# LPC4357_SDRAM.net
KiCad netlist of a schematic drawn in Altium Designer
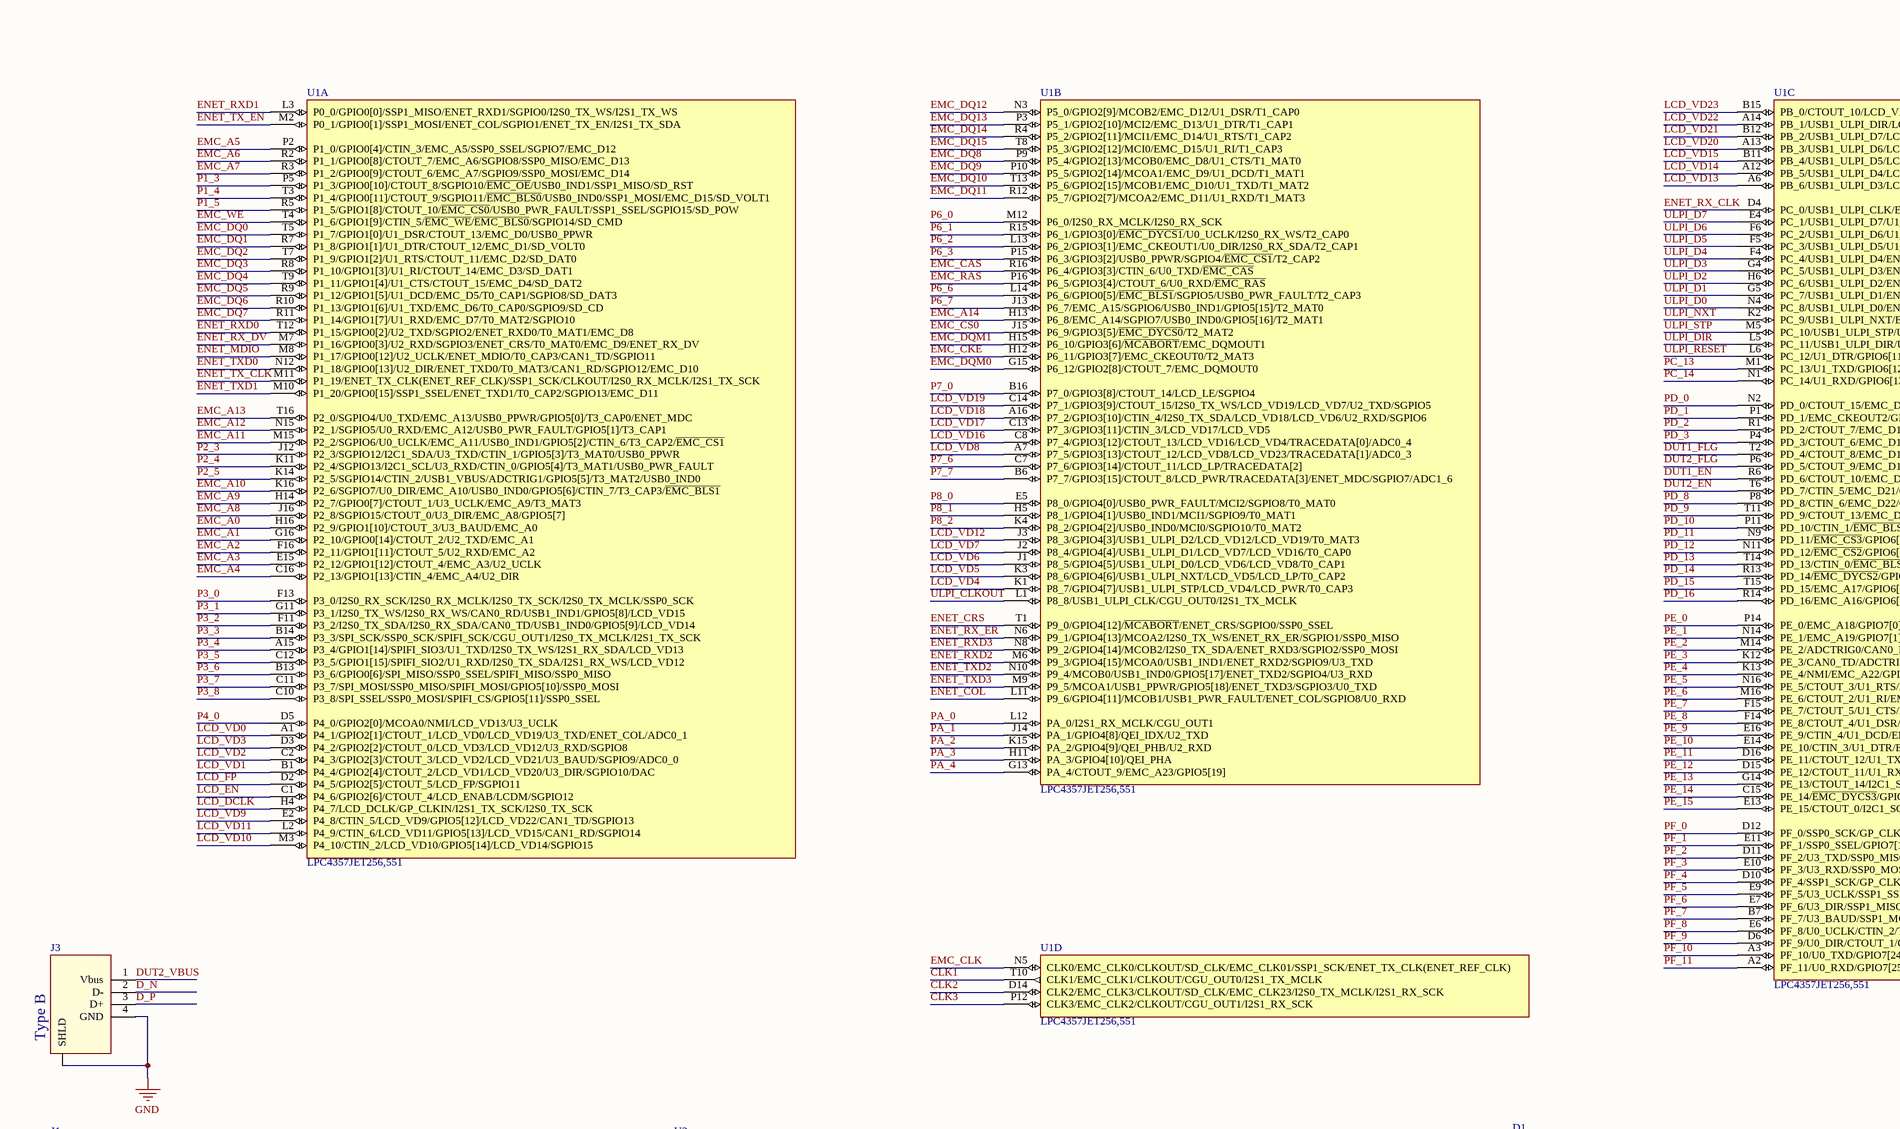
[diagram p0: LPC4357_SDRAM.SchDoc, top left]
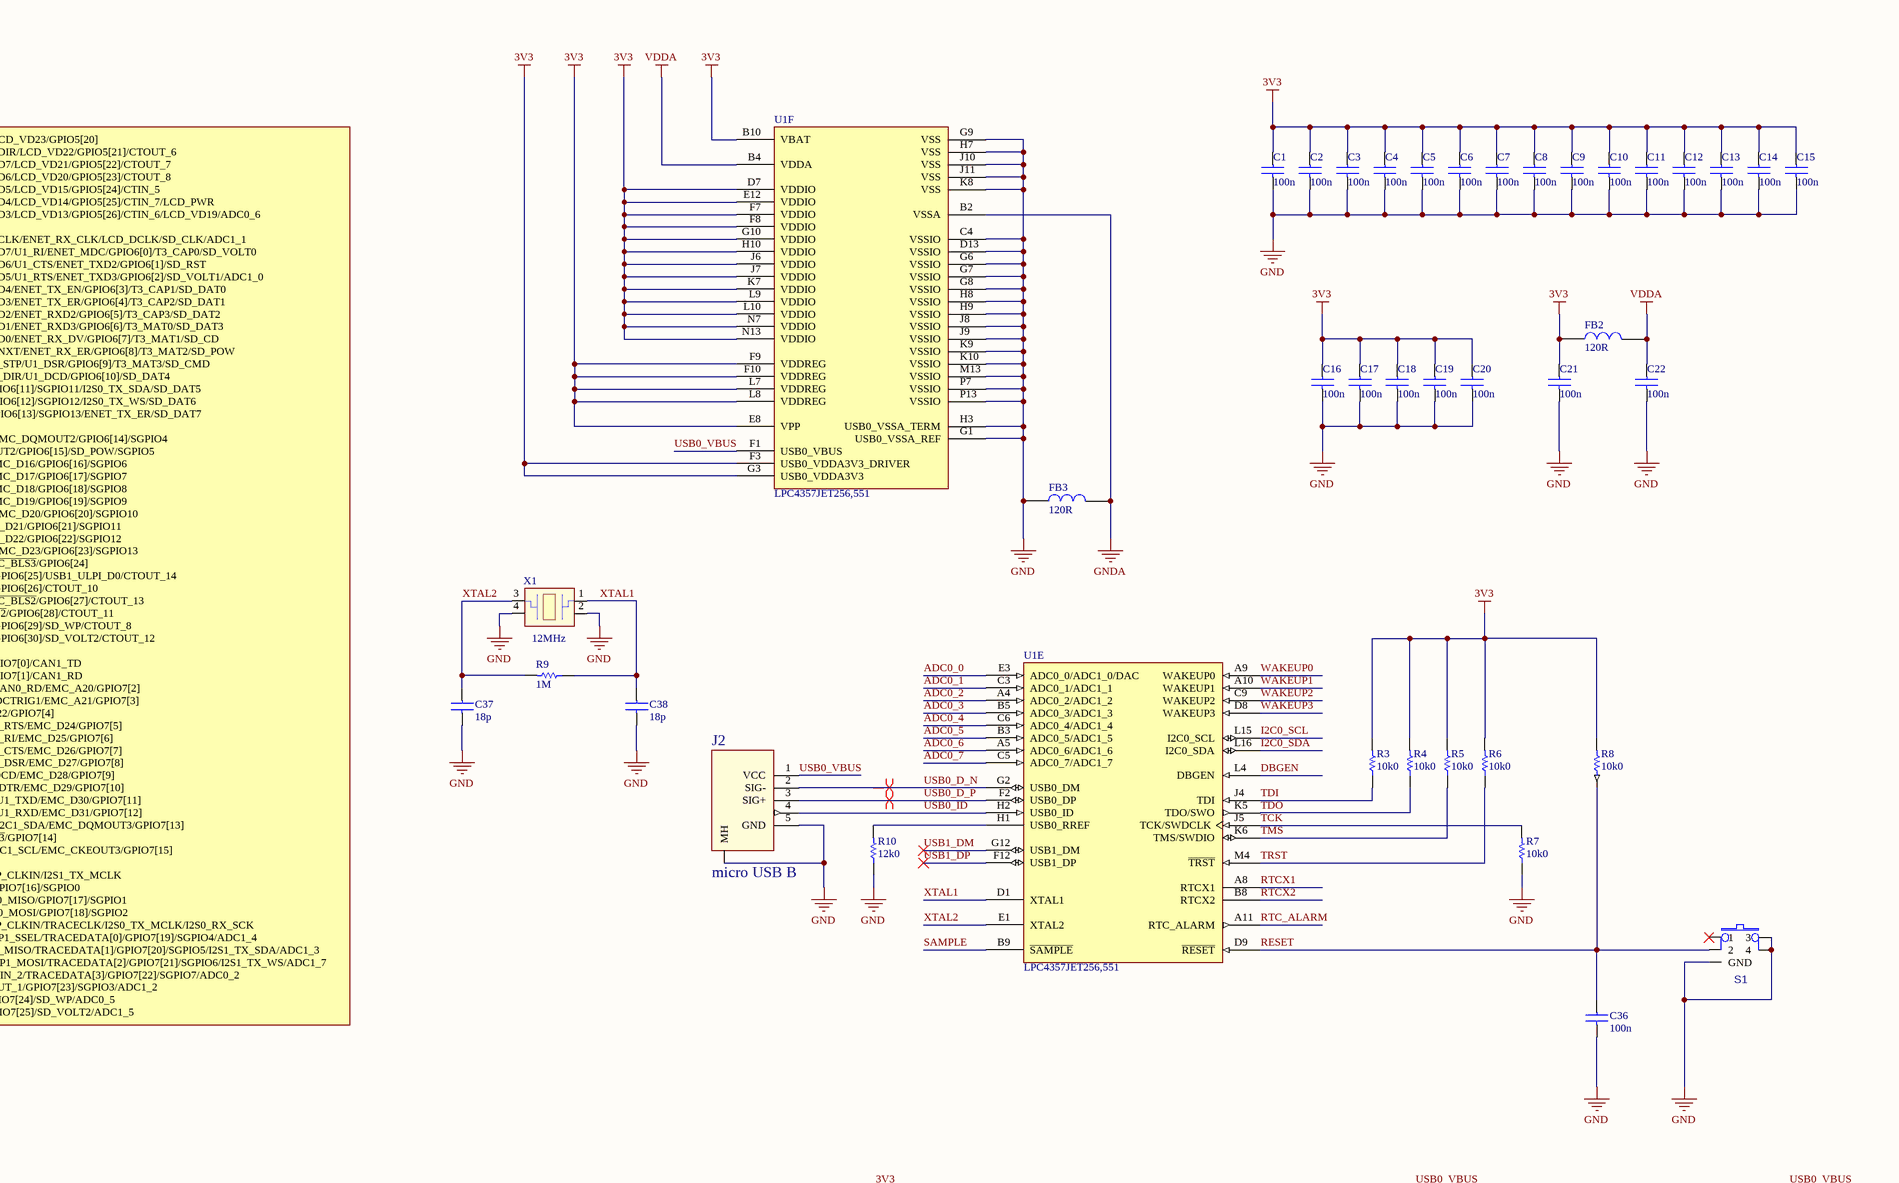
[diagram p1: LPC4357_SDRAM.SchDoc, top right]
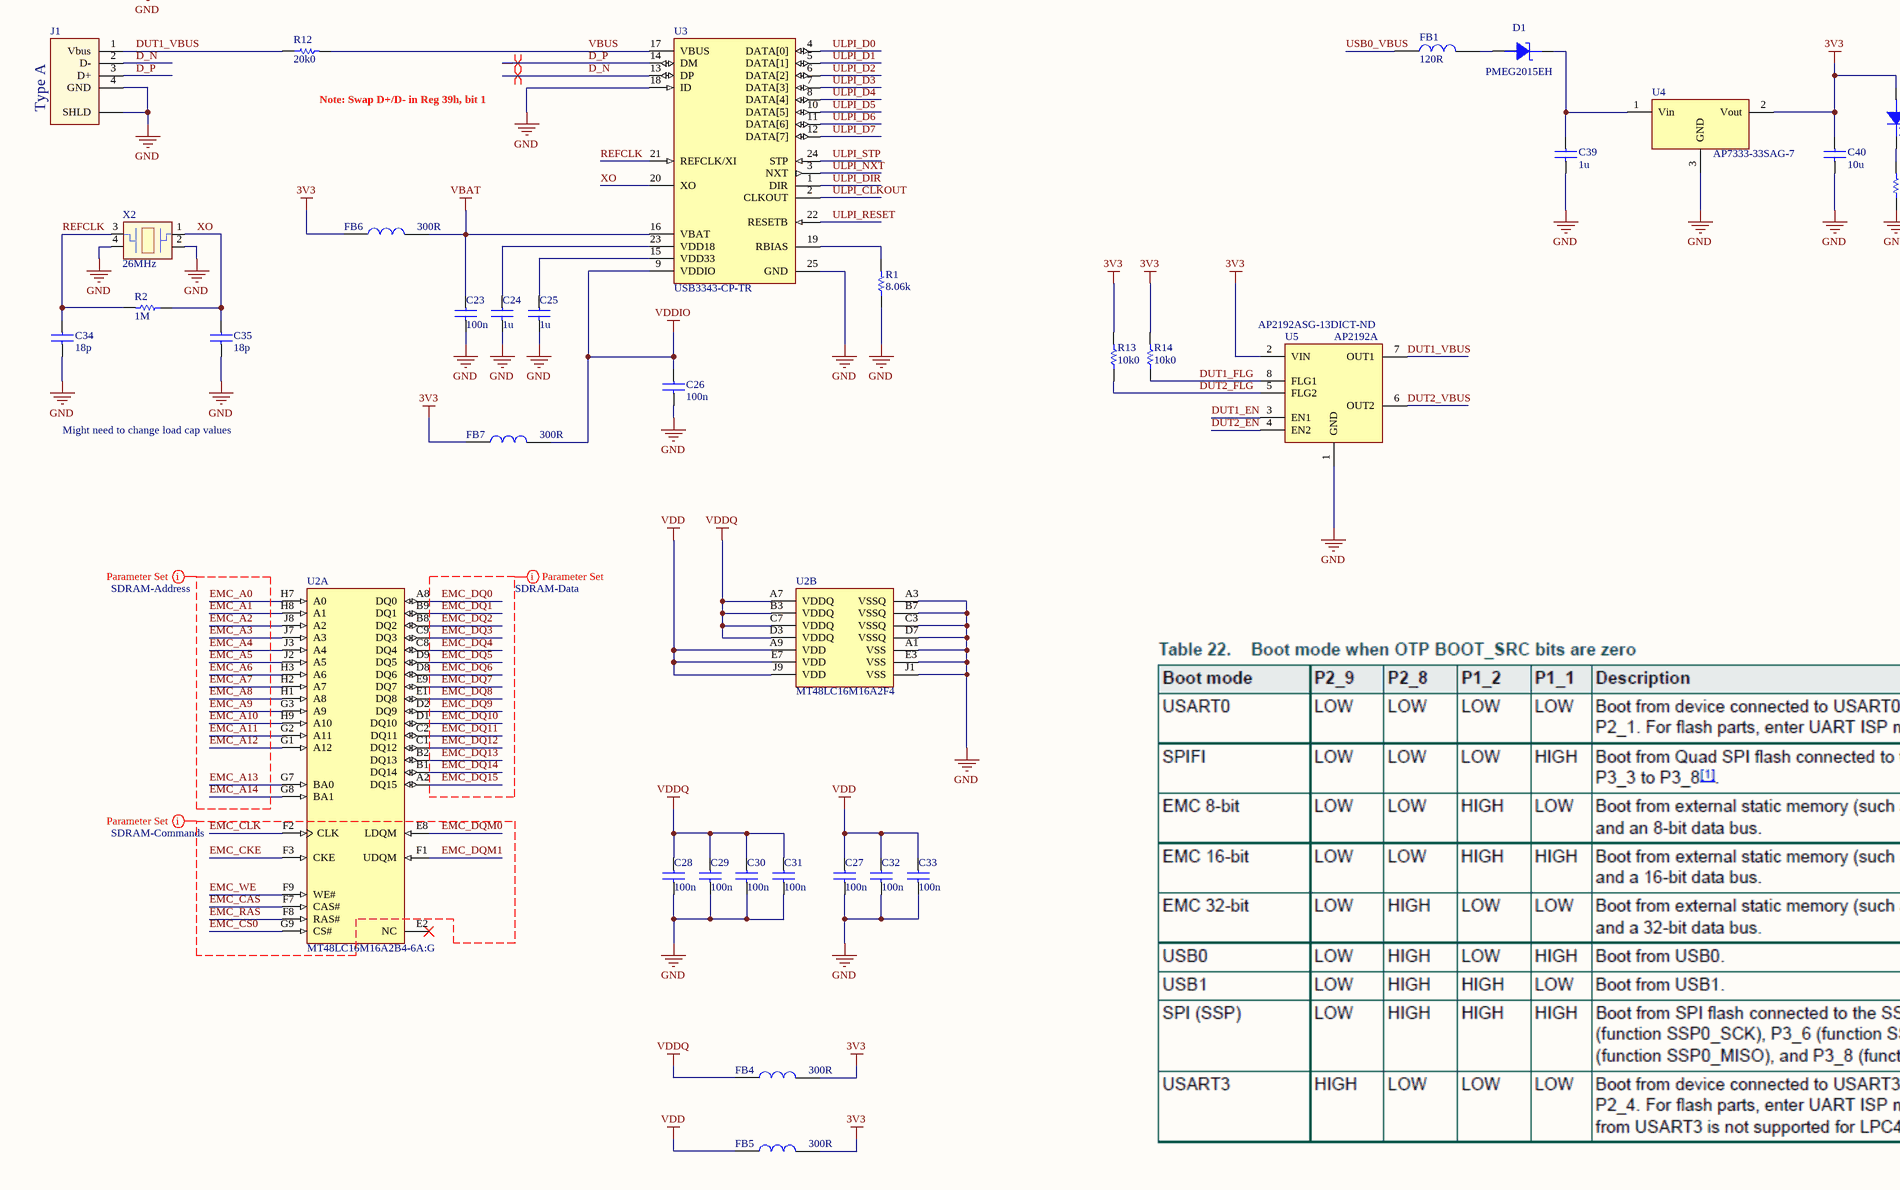
[diagram p2: LPC4357_SDRAM.SchDoc, bottom left]
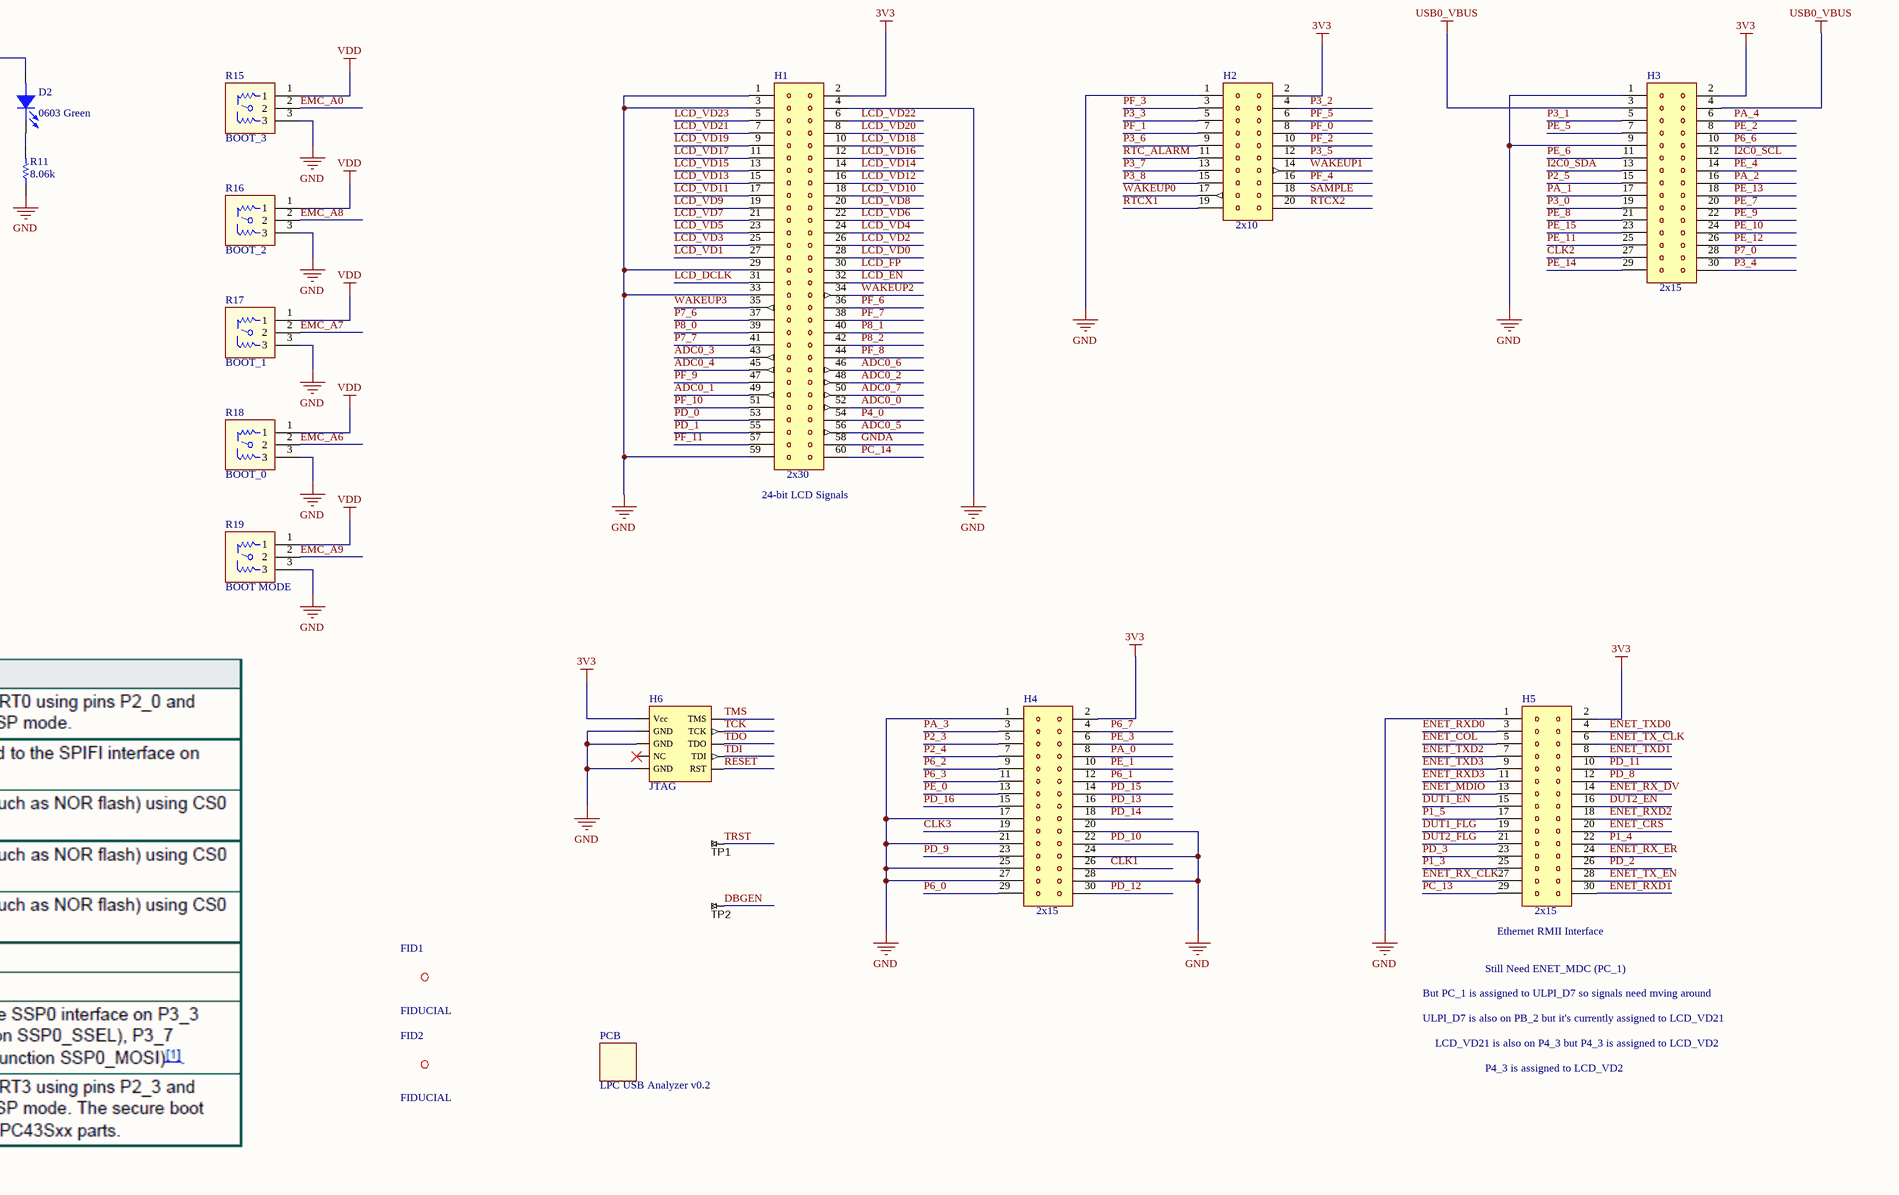
[diagram p3: LPC4357_SDRAM.SchDoc, bottom right]

(export (version "E")
  (design (tool "Eeschema 10.0.6"))
  (components
    (comp (ref "C1")
      (value "100n")
      (footprint "C_0402_N")
      (description "Cap, Chip, 100nF, 16V, ±10%, X7R, 0402")
      (fields (field (name "MANUFACTURER") "NIC"))
      (libsource (lib "GLIB") (part "C_100n_16V_10_0402_NIC"))
    )
    (comp (ref "C2")
      (value "100n")
      (footprint "C_0402_N")
      (description "Cap, Chip, 100nF, 16V, ±10%, X7R, 0402")
      (fields (field (name "MANUFACTURER") "NIC"))
      (libsource (lib "GLIB") (part "C_100n_16V_10_0402_NIC"))
    )
    (comp (ref "C3")
      (value "100n")
      (footprint "C_0402_N")
      (description "Cap, Chip, 100nF, 16V, ±10%, X7R, 0402")
      (fields (field (name "MANUFACTURER") "NIC"))
      (libsource (lib "GLIB") (part "C_100n_16V_10_0402_NIC"))
    )
    (comp (ref "C4")
      (value "100n")
      (footprint "C_0402_N")
      (description "Cap, Chip, 100nF, 16V, ±10%, X7R, 0402")
      (fields (field (name "MANUFACTURER") "NIC"))
      (libsource (lib "GLIB") (part "C_100n_16V_10_0402_NIC"))
    )
    (comp (ref "C5")
      (value "100n")
      (footprint "C_0402_N")
      (description "Cap, Chip, 100nF, 16V, ±10%, X7R, 0402")
      (fields (field (name "MANUFACTURER") "NIC"))
      (libsource (lib "GLIB") (part "C_100n_16V_10_0402_NIC"))
    )
    (comp (ref "C6")
      (value "100n")
      (footprint "C_0402_N")
      (description "Cap, Chip, 100nF, 16V, ±10%, X7R, 0402")
      (fields (field (name "MANUFACTURER") "NIC"))
      (libsource (lib "GLIB") (part "C_100n_16V_10_0402_NIC"))
    )
    (comp (ref "C7")
      (value "100n")
      (footprint "C_0402_N")
      (description "Cap, Chip, 100nF, 16V, ±10%, X7R, 0402")
      (fields (field (name "MANUFACTURER") "NIC"))
      (libsource (lib "GLIB") (part "C_100n_16V_10_0402_NIC"))
    )
    (comp (ref "C8")
      (value "100n")
      (footprint "C_0402_N")
      (description "Cap, Chip, 100nF, 16V, ±10%, X7R, 0402")
      (fields (field (name "MANUFACTURER") "NIC"))
      (libsource (lib "GLIB") (part "C_100n_16V_10_0402_NIC"))
    )
    (comp (ref "C9")
      (value "100n")
      (footprint "C_0402_N")
      (description "Cap, Chip, 100nF, 16V, ±10%, X7R, 0402")
      (fields (field (name "MANUFACTURER") "NIC"))
      (libsource (lib "GLIB") (part "C_100n_16V_10_0402_NIC"))
    )
    (comp (ref "C10")
      (value "100n")
      (footprint "C_0402_N")
      (description "Cap, Chip, 100nF, 16V, ±10%, X7R, 0402")
      (fields (field (name "MANUFACTURER") "NIC"))
      (libsource (lib "GLIB") (part "C_100n_16V_10_0402_NIC"))
    )
    (comp (ref "C11")
      (value "100n")
      (footprint "C_0402_N")
      (description "Cap, Chip, 100nF, 16V, ±10%, X7R, 0402")
      (fields (field (name "MANUFACTURER") "NIC"))
      (libsource (lib "GLIB") (part "C_100n_16V_10_0402_NIC"))
    )
    (comp (ref "C12")
      (value "100n")
      (footprint "C_0402_N")
      (description "Cap, Chip, 100nF, 16V, ±10%, X7R, 0402")
      (fields (field (name "MANUFACTURER") "NIC"))
      (libsource (lib "GLIB") (part "C_100n_16V_10_0402_NIC"))
    )
    (comp (ref "C13")
      (value "100n")
      (footprint "C_0402_N")
      (description "Cap, Chip, 100nF, 16V, ±10%, X7R, 0402")
      (fields (field (name "MANUFACTURER") "NIC"))
      (libsource (lib "GLIB") (part "C_100n_16V_10_0402_NIC"))
    )
    (comp (ref "C14")
      (value "100n")
      (footprint "C_0402_N")
      (description "Cap, Chip, 100nF, 16V, ±10%, X7R, 0402")
      (fields (field (name "MANUFACTURER") "NIC"))
      (libsource (lib "GLIB") (part "C_100n_16V_10_0402_NIC"))
    )
    (comp (ref "C15")
      (value "100n")
      (footprint "C_0402_N")
      (description "Cap, Chip, 100nF, 16V, ±10%, X7R, 0402")
      (fields (field (name "MANUFACTURER") "NIC"))
      (libsource (lib "GLIB") (part "C_100n_16V_10_0402_NIC"))
    )
    (comp (ref "C16")
      (value "100n")
      (footprint "C_0402_N")
      (description "Cap, Chip, 100nF, 16V, ±10%, X7R, 0402")
      (fields (field (name "MANUFACTURER") "NIC"))
      (libsource (lib "GLIB") (part "C_100n_16V_10_0402_NIC"))
    )
    (comp (ref "C17")
      (value "100n")
      (footprint "C_0402_N")
      (description "Cap, Chip, 100nF, 16V, ±10%, X7R, 0402")
      (fields (field (name "MANUFACTURER") "NIC"))
      (libsource (lib "GLIB") (part "C_100n_16V_10_0402_NIC"))
    )
    (comp (ref "C18")
      (value "100n")
      (footprint "C_0402_N")
      (description "Cap, Chip, 100nF, 16V, ±10%, X7R, 0402")
      (fields (field (name "MANUFACTURER") "NIC"))
      (libsource (lib "GLIB") (part "C_100n_16V_10_0402_NIC"))
    )
    (comp (ref "C19")
      (value "100n")
      (footprint "C_0402_N")
      (description "Cap, Chip, 100nF, 16V, ±10%, X7R, 0402")
      (fields (field (name "MANUFACTURER") "NIC"))
      (libsource (lib "GLIB") (part "C_100n_16V_10_0402_NIC"))
    )
    (comp (ref "C20")
      (value "100n")
      (footprint "C_0402_N")
      (description "Cap, Chip, 100nF, 16V, ±10%, X7R, 0402")
      (fields (field (name "MANUFACTURER") "NIC"))
      (libsource (lib "GLIB") (part "C_100n_16V_10_0402_NIC"))
    )
    (comp (ref "C21")
      (value "100n")
      (footprint "C_0402_N")
      (description "Cap, Chip, 100nF, 16V, ±10%, X7R, 0402")
      (fields (field (name "MANUFACTURER") "NIC"))
      (libsource (lib "GLIB") (part "C_100n_16V_10_0402_NIC"))
    )
    (comp (ref "C22")
      (value "100n")
      (footprint "C_0402_N")
      (description "Cap, Chip, 100nF, 16V, ±10%, X7R, 0402")
      (fields (field (name "MANUFACTURER") "NIC"))
      (libsource (lib "GLIB") (part "C_100n_16V_10_0402_NIC"))
    )
    (comp (ref "C23")
      (value "100n")
      (footprint "C_0402_N")
      (description "Cap, Chip, 100nF, 16V, ±10%, X7R, 0402")
      (fields (field (name "MANUFACTURER") "NIC"))
      (libsource (lib "GLIB") (part "C_100n_16V_10_0402_NIC"))
    )
    (comp (ref "C24")
      (value "1u")
      (footprint "C_0402_N")
      (description "Cap, Chip, 1uF, 10V, ±10%, X5R, 0402")
      (fields (field (name "MANUFACTURER") "NIC"))
      (libsource (lib "GLIB") (part "C_1u_10V_10_0402_NIC"))
    )
    (comp (ref "C25")
      (value "1u")
      (footprint "C_0402_N")
      (description "Cap, Chip, 1uF, 10V, ±10%, X5R, 0402")
      (fields (field (name "MANUFACTURER") "NIC"))
      (libsource (lib "GLIB") (part "C_1u_10V_10_0402_NIC"))
    )
    (comp (ref "C26")
      (value "100n")
      (footprint "C_0402_N")
      (description "Cap, Chip, 100nF, 16V, ±10%, X7R, 0402")
      (fields (field (name "MANUFACTURER") "NIC"))
      (libsource (lib "GLIB") (part "C_100n_16V_10_0402_NIC"))
    )
    (comp (ref "C27")
      (value "100n")
      (footprint "C_0402_N")
      (description "Cap, Chip, 100nF, 16V, ±10%, X7R, 0402")
      (fields (field (name "MANUFACTURER") "NIC"))
      (libsource (lib "GLIB") (part "C_100n_16V_10_0402_NIC"))
    )
    (comp (ref "C28")
      (value "100n")
      (footprint "C_0402_N")
      (description "Cap, Chip, 100nF, 16V, ±10%, X7R, 0402")
      (fields (field (name "MANUFACTURER") "NIC"))
      (libsource (lib "GLIB") (part "C_100n_16V_10_0402_NIC"))
    )
    (comp (ref "C29")
      (value "100n")
      (footprint "C_0402_N")
      (description "Cap, Chip, 100nF, 16V, ±10%, X7R, 0402")
      (fields (field (name "MANUFACTURER") "NIC"))
      (libsource (lib "GLIB") (part "C_100n_16V_10_0402_NIC"))
    )
    (comp (ref "C30")
      (value "100n")
      (footprint "C_0402_N")
      (description "Cap, Chip, 100nF, 16V, ±10%, X7R, 0402")
      (fields (field (name "MANUFACTURER") "NIC"))
      (libsource (lib "GLIB") (part "C_100n_16V_10_0402_NIC"))
    )
    (comp (ref "C31")
      (value "100n")
      (footprint "C_0402_N")
      (description "Cap, Chip, 100nF, 16V, ±10%, X7R, 0402")
      (fields (field (name "MANUFACTURER") "NIC"))
      (libsource (lib "GLIB") (part "C_100n_16V_10_0402_NIC"))
    )
    (comp (ref "C32")
      (value "100n")
      (footprint "C_0402_N")
      (description "Cap, Chip, 100nF, 16V, ±10%, X7R, 0402")
      (fields (field (name "MANUFACTURER") "NIC"))
      (libsource (lib "GLIB") (part "C_100n_16V_10_0402_NIC"))
    )
    (comp (ref "C33")
      (value "100n")
      (footprint "C_0402_N")
      (description "Cap, Chip, 100nF, 16V, ±10%, X7R, 0402")
      (fields (field (name "MANUFACTURER") "NIC"))
      (libsource (lib "GLIB") (part "C_100n_16V_10_0402_NIC"))
    )
    (comp (ref "C34")
      (value "18p")
      (footprint "C_0402_N")
      (description "Cap, Chip, 18pF, 50V, ±10%, NPO 0402")
      (fields (field (name "MANUFACTURER") "NIC"))
      (libsource (lib "GLIB") (part "C_18p_25V_10_0402_NIC"))
    )
    (comp (ref "C35")
      (value "18p")
      (footprint "C_0402_N")
      (description "Cap, Chip, 18pF, 50V, ±10%, NPO 0402")
      (fields (field (name "MANUFACTURER") "NIC"))
      (libsource (lib "GLIB") (part "C_18p_25V_10_0402_NIC"))
    )
    (comp (ref "C36")
      (value "100n")
      (footprint "C_0402_N")
      (description "Cap, Chip, 100nF, 16V, ±10%, X7R, 0402")
      (fields (field (name "MANUFACTURER") "NIC"))
      (libsource (lib "GLIB") (part "C_100n_16V_10_0402_NIC"))
    )
    (comp (ref "C37")
      (value "18p")
      (footprint "C_0402_N")
      (description "Cap, Chip, 18pF, 50V, ±10%, NPO 0402")
      (fields (field (name "MANUFACTURER") "NIC"))
      (libsource (lib "GLIB") (part "C_18p_25V_10_0402_NIC"))
    )
    (comp (ref "C38")
      (value "18p")
      (footprint "C_0402_N")
      (description "Cap, Chip, 18pF, 50V, ±10%, NPO 0402")
      (fields (field (name "MANUFACTURER") "NIC"))
      (libsource (lib "GLIB") (part "C_18p_25V_10_0402_NIC"))
    )
    (comp (ref "C39")
      (value "1u")
      (footprint "C_0402_N")
      (description "Cap, Chip, 1uF, 10V, ±10%, X5R, 0402")
      (fields (field (name "MANUFACTURER") "NIC"))
      (libsource (lib "GLIB") (part "C_1u_10V_10_0402_NIC"))
    )
    (comp (ref "C40")
      (value "10u")
      (footprint "0603x55")
      (description "Cap, Chip, 10uF, 10V, ± 15%, X5R, 0603")
      (fields (field (name "MANUFACTURER") "NIC"))
      (libsource (lib "GLIB") (part "C_10u_10V_10_0603_NIC"))
    )
    (comp (ref "D1")
      (value "PMEG2015EH")
      (footprint "SOD123F")
      (description "Diode, Schottky Rectifier, 20V, 1.5A, SOT123F")
      (fields (field (name "VOLTAGE") "20V") (field (name "MANUFACTURER") "NXP Semiconductors"))
      (libsource (lib "GLIB") (part "D_PMEG2015EH_20V_1A5_SOT123F"))
    )
    (comp (ref "D2")
      (value "0603 Green")
      (footprint "D_0603")
      (description "0603 LED, Green")
      (fields (field (name "MANUFACTURER") "Lite-on"))
      (libsource (lib "GLIB") (part "D_LED-0603_LTST-C190KGKT"))
    )
    (comp (ref "FB1")
      (value "120R")
      (footprint "L_0603")
      (description "Ferrite bead,120 ohm@100MHz,0.30 ohm @DC, 500mA, 0603")
      (fields (field (name "MANUFACTURER") "NIC"))
      (libsource (lib "GLIB") (part "FB_120R_0603_NIC"))
    )
    (comp (ref "FB2")
      (value "120R")
      (footprint "L_0603")
      (description "Ferrite bead,120 ohm@100MHz,0.30 ohm @DC, 500mA, 0603")
      (fields (field (name "MANUFACTURER") "NIC"))
      (libsource (lib "GLIB") (part "FB_120R_0603_NIC"))
    )
    (comp (ref "FB3")
      (value "120R")
      (footprint "L_0603")
      (description "Ferrite bead,120 ohm@100MHz,0.30 ohm @DC, 500mA, 0603")
      (fields (field (name "MANUFACTURER") "NIC"))
      (libsource (lib "GLIB") (part "FB_120R_0603_NIC"))
    )
    (comp (ref "FB4")
      (value "300R")
      (footprint "FB_0402-NIC")
      (description "Ferrite bead,300 ohm@100MHz,0.15 ohm @DC, 1A, 0402")
      (fields (field (name "MANUFACTURER") "NIC"))
      (libsource (lib "GLIB") (part "FB_300R_0402_NIC"))
    )
    (comp (ref "FB5")
      (value "300R")
      (footprint "FB_0402-NIC")
      (description "Ferrite bead,300 ohm@100MHz,0.15 ohm @DC, 1A, 0402")
      (fields (field (name "MANUFACTURER") "NIC"))
      (libsource (lib "GLIB") (part "FB_300R_0402_NIC"))
    )
    (comp (ref "FB6")
      (value "300R")
      (footprint "FB_0402-NIC")
      (description "Ferrite bead,300 ohm@100MHz,0.15 ohm @DC, 1A, 0402")
      (fields (field (name "MANUFACTURER") "NIC"))
      (libsource (lib "GLIB") (part "FB_300R_0402_NIC"))
    )
    (comp (ref "FB7")
      (value "300R")
      (footprint "FB_0402-NIC")
      (description "Ferrite bead,300 ohm@100MHz,0.15 ohm @DC, 1A, 0402")
      (fields (field (name "MANUFACTURER") "NIC"))
      (libsource (lib "GLIB") (part "FB_300R_0402_NIC"))
    )
    (comp (ref "FID1")
      (value "FIDUCIAL")
      (footprint "LFP113__FIDUCIAL")
      (description "SMD Device Fiducial")
      (libsource (lib "GLIB") (part "FIDUCIAL"))
    )
    (comp (ref "FID2")
      (value "FIDUCIAL")
      (footprint "LFP113__FIDUCIAL")
      (description "SMD Device Fiducial")
      (libsource (lib "GLIB") (part "FIDUCIAL"))
    )
    (comp (ref "H1")
      (value "2x30")
      (footprint "HDR_2x30_1.27mm")
      (description "CONN, Header, 2x30, TH, 1.27mm")
      (fields (field (name "MANUFACTURER") "Shenzhen Cankemeng"))
      (libsource (lib "GLIB") (part "JP_2x30_1.27mm"))
    )
    (comp (ref "H2")
      (value "2x10")
      (footprint "HDR_2x10_1.27mm")
      (description "CONN, Header, 2x10, TH, 1.27mm")
      (libsource (lib "GLIB") (part "JP_2x10_1.27mm"))
    )
    (comp (ref "H3")
      (value "2x15")
      (footprint "HDR_2x15_1.27mm")
      (description "CONN, Header, 2x15, TH, 1.27mm")
      (libsource (lib "GLIB") (part "JP_2x15_1.27mm"))
    )
    (comp (ref "H4")
      (value "2x15")
      (footprint "HDR_2x15_1.27mm")
      (description "CONN, Header, 2x15, TH, 1.27mm")
      (libsource (lib "GLIB") (part "JP_2x15_1.27mm"))
    )
    (comp (ref "H5")
      (value "2x15")
      (footprint "HDR_2x15_1.27mm")
      (description "CONN, Header, 2x15, TH, 1.27mm")
      (libsource (lib "GLIB") (part "JP_2x15_1.27mm"))
    )
    (comp (ref "H6")
      (value "JTAG")
      (footprint "JTAG_FTSH-105-01-XXX-D-K")
      (description "CONN, Header 2x5, TH, 1.27mm")
      (fields (field (name "MANUFACTURER") "Samtec"))
      (libsource (lib "GLIB") (part "JP_JTAG-FTSH_1.27"))
    )
    (comp (ref "J1")
      (value "Type A")
      (footprint "USB_A_F_SIDE_REVERSE_TH")
      (description "USB 2.0, Type A, Side Insert, Reverse Pinout, RA, TH")
      (fields (field (name "MANUFACTURER") "Jing Extension"))
      (libsource (lib "GLIB") (part "J_USB_A_Rotate_Reverse_TH"))
    )
    (comp (ref "J2")
      (value "micro USB B")
      (footprint "10118194")
      (description "USB 2.0, Micro USB, 5-pin, RA, SMT/TH")
      (fields (field (name "MANUFACTURER") "FCI"))
      (libsource (lib "GLIB") (part "J_microUSB_B_SMD-FCI"))
    )
    (comp (ref "J3")
      (value "Type B")
      (footprint "USB_B_F_RA_TH")
      (description "USB 2.0, Type B, RA, TH")
      (fields (field (name "MANUFACTURER") "FCI"))
      (libsource (lib "GLIB") (part "J_USB_B_2.0_RA"))
    )
    (comp (ref "PCB")
      (value "LPC USB Analyzer v0.2")
      (footprint "LOGO-GIO")
      (description "4 Layer Controlled Impedance PCB, ENIG")
      (fields (field (name "MANUFACTURER") "JLCPCB"))
      (libsource (lib "GLIB") (part "PCB"))
    )
    (comp (ref "R1")
      (value "8.06k")
      (footprint "R_0402-N")
      (description "Resistor, 8.06 kΩ, 1%, 0.06W, 0402")
      (fields (field (name "MANUFACTURER") "NIC"))
      (libsource (lib "GLIB") (part "Res Semi"))
    )
    (comp (ref "R2")
      (value "1M")
      (footprint "R_0402-N")
      (description "Resistor, 1 MΩ, 1%, 0.06W, 0402")
      (fields (field (name "MANUFACTURER") "NIC"))
      (libsource (lib "GLIB") (part "Res Semi"))
    )
    (comp (ref "R3")
      (value "10k0")
      (footprint "R_0402-N")
      (description "Resistor, 10.0 kΩ, 1%, 0.06W, 0402")
      (fields (field (name "MANUFACTURER") "NIC"))
      (libsource (lib "GLIB") (part "R_10k0_60mW_1_0402_NIC"))
    )
    (comp (ref "R4")
      (value "10k0")
      (footprint "R_0402-N")
      (description "Resistor, 10.0 kΩ, 1%, 0.06W, 0402")
      (fields (field (name "MANUFACTURER") "NIC"))
      (libsource (lib "GLIB") (part "R_10k0_60mW_1_0402_NIC"))
    )
    (comp (ref "R5")
      (value "10k0")
      (footprint "R_0402-N")
      (description "Resistor, 10.0 kΩ, 1%, 0.06W, 0402")
      (fields (field (name "MANUFACTURER") "NIC"))
      (libsource (lib "GLIB") (part "R_10k0_60mW_1_0402_NIC"))
    )
    (comp (ref "R6")
      (value "10k0")
      (footprint "R_0402-N")
      (description "Resistor, 10.0 kΩ, 1%, 0.06W, 0402")
      (fields (field (name "MANUFACTURER") "NIC"))
      (libsource (lib "GLIB") (part "R_10k0_60mW_1_0402_NIC"))
    )
    (comp (ref "R7")
      (value "10k0")
      (footprint "R_0402-N")
      (description "Resistor, 10.0 kΩ, 1%, 0.06W, 0402")
      (fields (field (name "MANUFACTURER") "NIC"))
      (libsource (lib "GLIB") (part "R_10k0_60mW_1_0402_NIC"))
    )
    (comp (ref "R8")
      (value "10k0")
      (footprint "R_0402-N")
      (description "Resistor, 10.0 kΩ, 1%, 0.06W, 0402")
      (fields (field (name "MANUFACTURER") "NIC"))
      (libsource (lib "GLIB") (part "R_10k0_60mW_1_0402_NIC"))
    )
    (comp (ref "R9")
      (value "1M")
      (footprint "R_0402-N")
      (description "Resistor, 1 MΩ, 1%, 0.06W, 0402")
      (fields (field (name "MANUFACTURER") "NIC"))
      (libsource (lib "GLIB") (part "Res Semi"))
    )
    (comp (ref "R10")
      (value "12k0")
      (footprint "R_0402-N")
      (description "Resistor, 12.0 kΩ, 1%, 0.06W, 0402")
      (fields (field (name "MANUFACTURER") "NIC"))
      (libsource (lib "GLIB") (part "R_12k0_60mW_1_0402_NIC"))
    )
    (comp (ref "R11")
      (value "8.06k")
      (footprint "R_0402-N")
      (description "Resistor, 8.06 kΩ, 1%, 0.06W, 0402")
      (fields (field (name "MANUFACTURER") "NIC"))
      (libsource (lib "GLIB") (part "Res Semi"))
    )
    (comp (ref "R12")
      (value "20k0")
      (footprint "R_0402-N")
      (description "Resistor, 20 kΩ, 1%, 0.06W, 0402")
      (fields (field (name "MANUFACTURER") "NIC"))
      (libsource (lib "GLIB") (part "R_20k0_100mW_1_0603_NIC"))
    )
    (comp (ref "R13")
      (value "10k0")
      (footprint "R_0402-N")
      (description "Resistor, 10.0 kΩ, 1%, 0.06W, 0402")
      (fields (field (name "MANUFACTURER") "NIC"))
      (libsource (lib "GLIB") (part "R_10k0_60mW_1_0402_NIC"))
    )
    (comp (ref "R14")
      (value "10k0")
      (footprint "R_0402-N")
      (description "Resistor, 10.0 kΩ, 1%, 0.06W, 0402")
      (fields (field (name "MANUFACTURER") "NIC"))
      (libsource (lib "GLIB") (part "R_10k0_60mW_1_0402_NIC"))
    )
    (comp (ref "R15")
      (value "BOOT_3")
      (footprint "3PAD_0402_JMP_1-2")
      (description "3-pad, 0402, jumper")
      (libsource (lib "GLIB") (part "CON_Jumper_3Pad_0402"))
    )
    (comp (ref "R16")
      (value "BOOT_2")
      (footprint "3PAD_0402_JMP_1-2")
      (description "3-pad, 0402, jumper")
      (libsource (lib "GLIB") (part "CON_Jumper_3Pad_0402"))
    )
    (comp (ref "R17")
      (value "BOOT_1")
      (footprint "3PAD_0402_JMP_1-2")
      (description "3-pad, 0402, jumper")
      (libsource (lib "GLIB") (part "CON_Jumper_3Pad_0402"))
    )
    (comp (ref "R18")
      (value "BOOT_0")
      (footprint "3PAD_0402_JMP_1-2")
      (description "3-pad, 0402, jumper")
      (libsource (lib "GLIB") (part "CON_Jumper_3Pad_0402"))
    )
    (comp (ref "R19")
      (value "BOOT MODE")
      (footprint "3PAD_0402_JMP_1-2")
      (description "3-pad, 0402, jumper")
      (libsource (lib "GLIB") (part "CON_Jumper_3Pad_0402"))
    )
    (comp (ref "S1")
      (value "PTS840")
      (footprint "SW_PTS840")
      (description "SWITCH SPST RA, 50mA, 24V, SMT")
      (fields (field (name "MANUFACTURER") "C&K"))
      (libsource (lib "GLIB") (part "SW_PTS840_RA_SMT"))
    )
    (comp (ref "TP1")
      (value "TP_60mil-pad")
      (footprint "TP-R50")
      (description "SMD test pin")
      (libsource (lib "GLIB") (part "TP_50mil-pad"))
    )
    (comp (ref "TP2")
      (value "TP_60mil-pad")
      (footprint "TP-R50")
      (description "SMD test pin")
      (libsource (lib "GLIB") (part "TP_50mil-pad"))
    )
    (comp (ref "U1")
      (value "LPC4357JET256,551")
      (footprint "NXP-SOT740-2")
      (description "32-bit ARM Cortex-M4 / M0 MCU, 164 I/O, 1024 KB Flash, 136 KB SRAM, LBGA-256")
      (fields (field (name "MANUFACTURER") "NXP Semiconductors") (field (name "PARTNUMBER") "LPC4357JET256"))
      (libsource (lib "GLIB") (part "U_LPC4357JET256_BGA256"))
    )
    (comp (ref "U2")
      (value "MT48LC16M16A2B4-6A:G")
      (footprint "VFBGA54_8x8")
      (description "256Mb 167MHz SDR SDRAM, 16Mb x 16, 5.4ns, 3.3V, VFBGA-54, 8x8")
      (fields
        (field (name "PARTNUMBER") "MT48LC16M16A2BG-75")
        (field (name "VOLTAGE") "3.3V")
        (field (name "MANUFACTURER") "Micron")
      )
      (libsource (lib "") (part "U_MT48LC16M16A2F4_VFBGA54_1"))
    )
    (comp (ref "U3")
      (value "USB3343-CP-TR")
      (footprint "MCHP-QFN-24_A_V")
      (description "Hi-Speed USB ULPI Transceiver, 1.8 to 3.3 V, QFN-24")
      (fields (field (name "MANUFACTURER") "Microchip"))
      (libsource (lib "GLIB") (part "U_USB3343_QFN24"))
    )
    (comp (ref "U4")
      (value "AP7333-33SAG-7")
      (footprint "SOT23_N")
      (description "IC, CONV DC/DC LDO 3.3V, 300mA, SOT23-3")
      (fields (field (name "MANUFACTURER") "STMicroelectronics"))
      (libsource (lib "GLIB") (part "U_AP7333-33SAG-7_SOT23-3"))
    )
    (comp (ref "U5")
      (value "AP2192A")
      (footprint "soic_8")
      (description "IC, USB Dual Switch w/ 1.5A Current Limit, SOIC-8")
      (fields
        (field (name "MANUFACTURER") "Diodes Inc")
        (field (name "SUPPLIER PART NUMBER 1") "AP2192ASG-13DICT-ND")
      )
      (libsource (lib "GLIB") (part "U_AP2192A_SOIC8"))
    )
    (comp (ref "X1")
      (value "12MHz")
      (description "X-tal, 12.000MHz, Cl=20pF, +-18ppm, 3225")
      (fields (field (name "MANUFACTURER") "ABRACON Co"))
      (libsource (lib "GLIB") (part "X_13.000MHZ_18pF_3225"))
    )
    (comp (ref "X2")
      (value "26MHz")
      (description "X-tal, 26.000MHz, Cl=6pF, +-18ppm, 2.0 x 1.6mm")
      (fields (field (name "MANUFACTURER") "muRata"))
      (libsource (lib "GLIB") (part "X_26.000MHZ_6pF_2016"))
    )
  )
  (nets
    (net (code "1") (name "/ADC0_0") (class "Default")
      (node (ref "H1") (pin "52") (pinfunction "52_52") (pintype "output"))
      (node (ref "U1") (pin "E3") (pinfunction "ADC0_0/ADC1_0/DAC_E3") (pintype "input"))
    )
    (net (code "2") (name "/ADC0_1") (class "Default")
      (node (ref "H1") (pin "49") (pinfunction "49_49") (pintype "output"))
      (node (ref "U1") (pin "C3") (pinfunction "ADC0_1/ADC1_1_C3") (pintype "input"))
    )
    (net (code "3") (name "/ADC0_2") (class "Default")
      (node (ref "H1") (pin "48") (pinfunction "48_48") (pintype "output"))
      (node (ref "U1") (pin "A4") (pinfunction "ADC0_2/ADC1_2_A4") (pintype "input"))
    )
    (net (code "4") (name "/ADC0_3") (class "Default")
      (node (ref "H1") (pin "43") (pinfunction "43_43") (pintype "output"))
      (node (ref "U1") (pin "B5") (pinfunction "ADC0_3/ADC1_3_B5") (pintype "input"))
    )
    (net (code "5") (name "/ADC0_4") (class "Default")
      (node (ref "H1") (pin "45") (pinfunction "45_45") (pintype "output"))
      (node (ref "U1") (pin "C6") (pinfunction "ADC0_4/ADC1_4_C6") (pintype "input"))
    )
    (net (code "6") (name "/ADC0_5") (class "Default")
      (node (ref "H1") (pin "56") (pinfunction "56_56") (pintype "output"))
      (node (ref "U1") (pin "B3") (pinfunction "ADC0_5/ADC1_5_B3") (pintype "input"))
    )
    (net (code "7") (name "/ADC0_6") (class "Default")
      (node (ref "H1") (pin "46") (pinfunction "46_46") (pintype "output"))
      (node (ref "U1") (pin "A5") (pinfunction "ADC0_6/ADC1_6_A5") (pintype "input"))
    )
    (net (code "8") (name "/ADC0_7") (class "Default")
      (node (ref "H1") (pin "50") (pinfunction "50_50") (pintype "output"))
      (node (ref "U1") (pin "C5") (pinfunction "ADC0_7/ADC1_7_C5") (pintype "input"))
    )
    (net (code "9") (name "/CLK1") (class "Default")
      (node (ref "H4") (pin "26") (pinfunction "26_26") (pintype "passive"))
      (node (ref "U1") (pin "T10") (pinfunction "CLK1/EMC_CLK1/CLKOUT/CGU_OUT0/I2S1_TX_MCLK_T10") (pintype "output"))
    )
    (net (code "10") (name "/CLK2") (class "Default")
      (node (ref "H3") (pin "27") (pinfunction "27_27") (pintype "passive"))
      (node (ref "U1") (pin "D14") (pinfunction "CLK2/EMC_CLK3/CLKOUT/SD_CLK/EMC_CLK23/I2S0_TX_MCLK/I2S1_RX_SCK_D14") (pintype "bidirectional"))
    )
    (net (code "11") (name "/CLK3") (class "Default")
      (node (ref "H4") (pin "19") (pinfunction "19_19") (pintype "passive"))
      (node (ref "U1") (pin "P12") (pinfunction "CLK3/EMC_CLK2/CLKOUT/CGU_OUT1/I2S1_RX_SCK_P12") (pintype "bidirectional"))
    )
    (net (code "12") (name "/DBGEN") (class "Default")
      (node (ref "TP2") (pin "1") (pintype "output"))
      (node (ref "U1") (pin "L4") (pinfunction "DBGEN_L4") (pintype "input"))
    )
    (net (code "13") (name "/DUT1_EN") (class "Default")
      (node (ref "H5") (pin "15") (pinfunction "15_15") (pintype "passive"))
      (node (ref "U1") (pin "R6") (pinfunction "PD_6/CTOUT_10/EMC_D20/GPIO6[20]/SGPIO10_R6") (pintype "bidirectional"))
      (node (ref "U5") (pin "3") (pinfunction "EN1_3") (pintype "passive"))
    )
    (net (code "14") (name "/DUT1_FLG") (class "Default")
      (node (ref "H5") (pin "19") (pinfunction "19_19") (pintype "passive"))
      (node (ref "R14") (pin "1") (pinfunction "1_1") (pintype "passive"))
      (node (ref "U1") (pin "T2") (pinfunction "PD_4/CTOUT_8/EMC_D18/GPIO6[18]/SGPIO8_T2") (pintype "bidirectional"))
      (node (ref "U5") (pin "8") (pinfunction "FLG1_8") (pintype "passive"))
    )
    (net (code "15") (name "/DUT1_VBUS") (class "Default")
      (node (ref "J1") (pin "1") (pinfunction "Vbus_1") (pintype "power_in"))
      (node (ref "R12") (pin "1") (pinfunction "1_1") (pintype "passive"))
      (node (ref "U5") (pin "7") (pinfunction "OUT1_7") (pintype "power_in"))
    )
    (net (code "16") (name "/DUT2_EN") (class "Default")
      (node (ref "H5") (pin "16") (pinfunction "16_16") (pintype "passive"))
      (node (ref "U1") (pin "T6") (pinfunction "PD_7/CTIN_5/EMC_D21/GPIO6[21]/SGPIO11_T6") (pintype "bidirectional"))
      (node (ref "U5") (pin "4") (pinfunction "EN2_4") (pintype "passive"))
    )
    (net (code "17") (name "/DUT2_FLG") (class "Default")
      (node (ref "H5") (pin "21") (pinfunction "21_21") (pintype "passive"))
      (node (ref "R13") (pin "1") (pinfunction "1_1") (pintype "passive"))
      (node (ref "U1") (pin "P6") (pinfunction "PD_5/CTOUT_9/EMC_D19/GPIO6[19]/SGPIO9_P6") (pintype "bidirectional"))
      (node (ref "U5") (pin "5") (pinfunction "FLG2_5") (pintype "passive"))
    )
    (net (code "18") (name "/DUT2_VBUS") (class "Default")
      (node (ref "J3") (pin "1") (pinfunction "Vbus_1") (pintype "passive"))
      (node (ref "U5") (pin "6") (pinfunction "OUT2_6") (pintype "power_in"))
    )
    (net (code "19") (name "/D_N") (class "Default")
      (node (ref "J1") (pin "2") (pinfunction "D-_2") (pintype "passive"))
      (node (ref "J3") (pin "2") (pinfunction "D-_2") (pintype "passive"))
      (node (ref "U3") (pin "13") (pinfunction "DP_13") (pintype "bidirectional"))
    )
    (net (code "20") (name "/D_P") (class "Default")
      (node (ref "J1") (pin "3") (pinfunction "D+_3") (pintype "passive"))
      (node (ref "J3") (pin "3") (pinfunction "D+_3") (pintype "passive"))
      (node (ref "U3") (pin "14") (pinfunction "DM_14") (pintype "bidirectional"))
    )
    (net (code "21") (name "/EMC_A0") (class "Default")
      (node (ref "R15") (pin "2") (pinfunction "2_2") (pintype "passive"))
      (node (ref "U1") (pin "H16") (pinfunction "P2_9/GPIO1[10]/CTOUT_3/U3_BAUD/EMC_A0_H16") (pintype "bidirectional"))
      (node (ref "U2") (pin "H7") (pinfunction "A0_H7") (pintype "input"))
    )
    (net (code "22") (name "/EMC_A1") (class "Default")
      (node (ref "U1") (pin "G16") (pinfunction "P2_10/GPIO0[14]/CTOUT_2/U2_TXD/EMC_A1_G16") (pintype "bidirectional"))
      (node (ref "U2") (pin "H8") (pinfunction "A1_H8") (pintype "input"))
    )
    (net (code "23") (name "/EMC_A2") (class "Default")
      (node (ref "U1") (pin "F16") (pinfunction "P2_11/GPIO1[11]/CTOUT_5/U2_RXD/EMC_A2_F16") (pintype "bidirectional"))
      (node (ref "U2") (pin "J8") (pinfunction "A2_J8") (pintype "input"))
    )
    (net (code "24") (name "/EMC_A3") (class "Default")
      (node (ref "U1") (pin "E15") (pinfunction "P2_12/GPIO1[12]/CTOUT_4/EMC_A3/U2_UCLK_E15") (pintype "bidirectional"))
      (node (ref "U2") (pin "J7") (pinfunction "A3_J7") (pintype "input"))
    )
    (net (code "25") (name "/EMC_A4") (class "Default")
      (node (ref "U1") (pin "C16") (pinfunction "P2_13/GPIO1[13]/CTIN_4/EMC_A4/U2_DIR_C16") (pintype "bidirectional"))
      (node (ref "U2") (pin "J3") (pinfunction "A4_J3") (pintype "input"))
    )
    (net (code "26") (name "/EMC_A5") (class "Default")
      (node (ref "U1") (pin "P2") (pinfunction "P1_0/GPIO0[4]/CTIN_3/EMC_A5/SSP0_SSEL/SGPIO7/EMC_D12_P2") (pintype "bidirectional"))
      (node (ref "U2") (pin "J2") (pinfunction "A5_J2") (pintype "input"))
    )
    (net (code "27") (name "/EMC_A6") (class "Default")
      (node (ref "R18") (pin "2") (pinfunction "2_2") (pintype "passive"))
      (node (ref "U1") (pin "R2") (pinfunction "P1_1/GPIO0[8]/CTOUT_7/EMC_A6/SGPIO8/SSP0_MISO/EMC_D13_R2") (pintype "bidirectional"))
      (node (ref "U2") (pin "H3") (pinfunction "A6_H3") (pintype "input"))
    )
    (net (code "28") (name "/EMC_A7") (class "Default")
      (node (ref "R17") (pin "2") (pinfunction "2_2") (pintype "passive"))
      (node (ref "U1") (pin "R3") (pinfunction "P1_2/GPIO0[9]/CTOUT_6/EMC_A7/SGPIO9/SSP0_MOSI/EMC_D14_R3") (pintype "bidirectional"))
      (node (ref "U2") (pin "H2") (pinfunction "A7_H2") (pintype "input"))
    )
    (net (code "29") (name "/EMC_A8") (class "Default")
      (node (ref "R16") (pin "2") (pinfunction "2_2") (pintype "passive"))
      (node (ref "U1") (pin "J16") (pinfunction "P2_8/SGPIO15/CTOUT_0/U3_DIR/EMC_A8/GPIO5[7]_J16") (pintype "bidirectional"))
      (node (ref "U2") (pin "H1") (pinfunction "A8_H1") (pintype "input"))
    )
    (net (code "30") (name "/EMC_A9") (class "Default")
      (node (ref "R19") (pin "2") (pinfunction "2_2") (pintype "passive"))
      (node (ref "U1") (pin "H14") (pinfunction "P2_7/GPIO0[7]/CTOUT_1/U3_UCLK/EMC_A9/T3_MAT3_H14") (pintype "bidirectional"))
      (node (ref "U2") (pin "G3") (pinfunction "A9_G3") (pintype "input"))
    )
    (net (code "31") (name "/EMC_A10") (class "Default")
      (node (ref "U1") (pin "K16") (pinfunction "P2_6/SGPIO7/U0_DIR/EMC_A10/USB0_IND0/GPIO5[6]/CTIN_7/T3_CAP3/~{EMC_BLS1}_K16") (pintype "bidirectional"))
      (node (ref "U2") (pin "H9") (pinfunction "A10_H9") (pintype "input"))
    )
    (net (code "32") (name "/EMC_A11") (class "Default")
      (node (ref "U1") (pin "M15") (pinfunction "P2_2/SGPIO6/U0_UCLK/EMC_A11/USB0_IND1/GPIO5[2]/CTIN_6/T3_CAP2/~{EMC_CS1}_M15") (pintype "bidirectional"))
      (node (ref "U2") (pin "G2") (pinfunction "A11_G2") (pintype "input"))
    )
    (net (code "33") (name "/EMC_A12") (class "Default")
      (node (ref "U1") (pin "N15") (pinfunction "P2_1/SGPIO5/U0_RXD/EMC_A12/USB0_PWR_FAULT/GPIO5[1]/T3_CAP1_N15") (pintype "bidirectional"))
      (node (ref "U2") (pin "G1") (pinfunction "A12_G1") (pintype "input"))
    )
    (net (code "34") (name "/EMC_A13") (class "Default")
      (node (ref "U1") (pin "T16") (pinfunction "P2_0/SGPIO4/U0_TXD/EMC_A13/USB0_PPWR/GPIO5[0]/T3_CAP0/ENET_MDC_T16") (pintype "bidirectional"))
      (node (ref "U2") (pin "G7") (pinfunction "BA0_G7") (pintype "input"))
    )
    (net (code "35") (name "/EMC_A14") (class "Default")
      (node (ref "U1") (pin "H13") (pinfunction "P6_8/EMC_A14/SGPIO7/USB0_IND0/GPIO5[16]/T2_MAT1_H13") (pintype "bidirectional"))
      (node (ref "U2") (pin "G8") (pinfunction "BA1_G8") (pintype "input"))
    )
    (net (code "36") (name "/EMC_CAS") (class "Default")
      (node (ref "U1") (pin "R16") (pinfunction "P6_4/GPIO3[3]/CTIN_6/U0_TXD/~{EMC_CAS}_R16") (pintype "bidirectional"))
      (node (ref "U2") (pin "F7") (pinfunction "CAS#_F7") (pintype "input"))
    )
    (net (code "37") (name "/EMC_CKE") (class "Default")
      (node (ref "U1") (pin "H12") (pinfunction "P6_11/GPIO3[7]/EMC_CKEOUT0/T2_MAT3_H12") (pintype "bidirectional"))
      (node (ref "U2") (pin "F3") (pinfunction "CKE_F3") (pintype "input"))
    )
    (net (code "38") (name "/EMC_CLK") (class "Default")
      (node (ref "U1") (pin "N5") (pinfunction "CLK0/EMC_CLK0/CLKOUT/SD_CLK/EMC_CLK01/SSP1_SCK/ENET_TX_CLK(ENET_REF_CLK)_N5") (pintype "bidirectional"))
      (node (ref "U2") (pin "F2") (pinfunction "CLK_F2") (pintype "input"))
    )
    (net (code "39") (name "/EMC_CS0") (class "Default")
      (node (ref "U1") (pin "J15") (pinfunction "P6_9/GPIO3[5]/~{EMC_DYCS0}/T2_MAT2_J15") (pintype "bidirectional"))
      (node (ref "U2") (pin "G9") (pinfunction "CS#_G9") (pintype "input"))
    )
    (net (code "40") (name "/EMC_DQ0") (class "Default")
      (node (ref "U1") (pin "T5") (pinfunction "P1_7/GPIO1[0]/U1_DSR/CTOUT_13/EMC_D0/USB0_PPWR_T5") (pintype "bidirectional"))
      (node (ref "U2") (pin "A8") (pinfunction "DQ0_A8") (pintype "bidirectional"))
    )
    (net (code "41") (name "/EMC_DQ1") (class "Default")
      (node (ref "U1") (pin "R7") (pinfunction "P1_8/GPIO1[1]/U1_DTR/CTOUT_12/EMC_D1/SD_VOLT0_R7") (pintype "bidirectional"))
      (node (ref "U2") (pin "B9") (pinfunction "DQ1_B9") (pintype "bidirectional"))
    )
    (net (code "42") (name "/EMC_DQ2") (class "Default")
      (node (ref "U1") (pin "T7") (pinfunction "P1_9/GPIO1[2]/U1_RTS/CTOUT_11/EMC_D2/SD_DAT0_T7") (pintype "bidirectional"))
      (node (ref "U2") (pin "B8") (pinfunction "DQ2_B8") (pintype "bidirectional"))
    )
    (net (code "43") (name "/EMC_DQ3") (class "Default")
      (node (ref "U1") (pin "R8") (pinfunction "P1_10/GPIO1[3]/U1_RI/CTOUT_14/EMC_D3/SD_DAT1_R8") (pintype "bidirectional"))
      (node (ref "U2") (pin "C9") (pinfunction "DQ3_C9") (pintype "bidirectional"))
    )
    (net (code "44") (name "/EMC_DQ4") (class "Default")
      (node (ref "U1") (pin "T9") (pinfunction "P1_11/GPIO1[4]/U1_CTS/CTOUT_15/EMC_D4/SD_DAT2_T9") (pintype "bidirectional"))
      (node (ref "U2") (pin "C8") (pinfunction "DQ4_C8") (pintype "bidirectional"))
    )
    (net (code "45") (name "/EMC_DQ5") (class "Default")
      (node (ref "U1") (pin "R9") (pinfunction "P1_12/GPIO1[5]/U1_DCD/EMC_D5/T0_CAP1/SGPIO8/SD_DAT3_R9") (pintype "bidirectional"))
      (node (ref "U2") (pin "D9") (pinfunction "DQ5_D9") (pintype "bidirectional"))
    )
    (net (code "46") (name "/EMC_DQ6") (class "Default")
      (node (ref "U1") (pin "R10") (pinfunction "P1_13/GPIO1[6]/U1_TXD/EMC_D6/T0_CAP0/SGPIO9/SD_CD_R10") (pintype "bidirectional"))
      (node (ref "U2") (pin "D8") (pinfunction "DQ6_D8") (pintype "bidirectional"))
    )
    (net (code "47") (name "/EMC_DQ7") (class "Default")
      (node (ref "U1") (pin "R11") (pinfunction "P1_14/GPIO1[7]/U1_RXD/EMC_D7/T0_MAT2/SGPIO10_R11") (pintype "bidirectional"))
      (node (ref "U2") (pin "E9") (pinfunction "DQ7_E9") (pintype "bidirectional"))
    )
    (net (code "48") (name "/EMC_DQ8") (class "Default")
      (node (ref "U1") (pin "P9") (pinfunction "P5_4/GPIO2[13]/MCOB0/EMC_D8/U1_CTS/T1_MAT0_P9") (pintype "bidirectional"))
      (node (ref "U2") (pin "E1") (pinfunction "DQ8_E1") (pintype "bidirectional"))
    )
    (net (code "49") (name "/EMC_DQ9") (class "Default")
      (node (ref "U1") (pin "P10") (pinfunction "P5_5/GPIO2[14]/MCOA1/EMC_D9/U1_DCD/T1_MAT1_P10") (pintype "bidirectional"))
      (node (ref "U2") (pin "D2") (pinfunction "DQ9_D2") (pintype "bidirectional"))
    )
    (net (code "50") (name "/EMC_DQ10") (class "Default")
      (node (ref "U1") (pin "T13") (pinfunction "P5_6/GPIO2[15]/MCOB1/EMC_D10/U1_TXD/T1_MAT2_T13") (pintype "bidirectional"))
      (node (ref "U2") (pin "D1") (pinfunction "DQ10_D1") (pintype "bidirectional"))
    )
    (net (code "51") (name "/EMC_DQ11") (class "Default")
      (node (ref "U1") (pin "R12") (pinfunction "P5_7/GPIO2[7]/MCOA2/EMC_D11/U1_RXD/T1_MAT3_R12") (pintype "bidirectional"))
      (node (ref "U2") (pin "C2") (pinfunction "DQ11_C2") (pintype "bidirectional"))
    )
    (net (code "52") (name "/EMC_DQ12") (class "Default")
      (node (ref "U1") (pin "N3") (pinfunction "P5_0/GPIO2[9]/MCOB2/EMC_D12/U1_DSR/T1_CAP0_N3") (pintype "bidirectional"))
      (node (ref "U2") (pin "C1") (pinfunction "DQ12_C1") (pintype "bidirectional"))
    )
    (net (code "53") (name "/EMC_DQ13") (class "Default")
      (node (ref "U1") (pin "P3") (pinfunction "P5_1/GPIO2[10]/MCI2/EMC_D13/U1_DTR/T1_CAP1_P3") (pintype "bidirectional"))
      (node (ref "U2") (pin "B2") (pinfunction "DQ13_B2") (pintype "bidirectional"))
    )
    (net (code "54") (name "/EMC_DQ14") (class "Default")
      (node (ref "U1") (pin "R4") (pinfunction "P5_2/GPIO2[11]/MCI1/EMC_D14/U1_RTS/T1_CAP2_R4") (pintype "bidirectional"))
      (node (ref "U2") (pin "B1") (pinfunction "DQ14_B1") (pintype "bidirectional"))
    )
    (net (code "55") (name "/EMC_DQ15") (class "Default")
      (node (ref "U1") (pin "T8") (pinfunction "P5_3/GPIO2[12]/MCI0/EMC_D15/U1_RI/T1_CAP3_T8") (pintype "bidirectional"))
      (node (ref "U2") (pin "A2") (pinfunction "DQ15_A2") (pintype "bidirectional"))
    )
    (net (code "56") (name "/EMC_DQM0") (class "Default")
      (node (ref "U1") (pin "G15") (pinfunction "P6_12/GPIO2[8]/CTOUT_7/EMC_DQMOUT0_G15") (pintype "bidirectional"))
      (node (ref "U2") (pin "E8") (pinfunction "LDQM_E8") (pintype "input"))
    )
    (net (code "57") (name "/EMC_DQM1") (class "Default")
      (node (ref "U1") (pin "H15") (pinfunction "P6_10/GPIO3[6]/~{MCABORT}/EMC_DQMOUT1_H15") (pintype "bidirectional"))
      (node (ref "U2") (pin "F1") (pinfunction "UDQM_F1") (pintype "input"))
    )
    (net (code "58") (name "/EMC_RAS") (class "Default")
      (node (ref "U1") (pin "P16") (pinfunction "P6_5/GPIO3[4]/CTOUT_6/U0_RXD/~{EMC_RAS}_P16") (pintype "bidirectional"))
      (node (ref "U2") (pin "F8") (pinfunction "RAS#_F8") (pintype "input"))
    )
    (net (code "59") (name "/EMC_WE") (class "Default")
      (node (ref "U1") (pin "T4") (pinfunction "P1_6/GPIO1[9]/CTIN_5/~{EMC_WE}/~{EMC_BLS0}/SGPIO14/SD_CMD_T4") (pintype "bidirectional"))
      (node (ref "U2") (pin "F9") (pinfunction "WE#_F9") (pintype "input"))
    )
    (net (code "60") (name "/ENET_COL") (class "Default")
      (node (ref "H5") (pin "5") (pinfunction "5_5") (pintype "passive"))
      (node (ref "U1") (pin "L11") (pinfunction "P9_6/GPIO4[11]/MCOB1/USB1_PWR_FAULT/ENET_COL/SGPIO8/U0_RXD_L11") (pintype "bidirectional"))
    )
    (net (code "61") (name "/ENET_CRS") (class "Default")
      (node (ref "H5") (pin "20") (pinfunction "20_20") (pintype "passive"))
      (node (ref "U1") (pin "T1") (pinfunction "P9_0/GPIO4[12]/~{MCABORT}/ENET_CRS/SGPIO0/SSP0_SSEL_T1") (pintype "bidirectional"))
    )
    (net (code "62") (name "/ENET_MDIO") (class "Default")
      (node (ref "H5") (pin "13") (pinfunction "13_13") (pintype "passive"))
      (node (ref "U1") (pin "M8") (pinfunction "P1_17/GPIO0[12]/U2_UCLK/ENET_MDIO/T0_CAP3/CAN1_TD/SGPIO11_M8") (pintype "bidirectional"))
    )
    (net (code "63") (name "/ENET_RXD0") (class "Default")
      (node (ref "H5") (pin "3") (pinfunction "3_3") (pintype "passive"))
      (node (ref "U1") (pin "T12") (pinfunction "P1_15/GPIO0[2]/U2_TXD/SGPIO2/ENET_RXD0/T0_MAT1/EMC_D8_T12") (pintype "bidirectional"))
    )
    (net (code "64") (name "/ENET_RXD1") (class "Default")
      (node (ref "H5") (pin "30") (pinfunction "30_30") (pintype "passive"))
      (node (ref "U1") (pin "L3") (pinfunction "P0_0/GPIO0[0]/SSP1_MISO/ENET_RXD1/SGPIO0/I2S0_TX_WS/I2S1_TX_WS_L3") (pintype "bidirectional"))
    )
    (net (code "65") (name "/ENET_RXD2") (class "Default")
      (node (ref "H5") (pin "18") (pinfunction "18_18") (pintype "passive"))
      (node (ref "U1") (pin "M6") (pinfunction "P9_3/GPIO4[15]/MCOA0/USB1_IND1/ENET_RXD2/SGPIO9/U3_TXD_M6") (pintype "bidirectional"))
    )
    (net (code "66") (name "/ENET_RXD3") (class "Default")
      (node (ref "H5") (pin "11") (pinfunction "11_11") (pintype "passive"))
      (node (ref "U1") (pin "N8") (pinfunction "P9_2/GPIO4[14]/MCOB2/I2S0_TX_SDA/ENET_RXD3/SGPIO2/SSP0_MOSI_N8") (pintype "bidirectional"))
    )
    (net (code "67") (name "/ENET_RX_CLK") (class "Default")
      (node (ref "H5") (pin "27") (pinfunction "27_27") (pintype "passive"))
      (node (ref "U1") (pin "D4") (pinfunction "PC_0/USB1_ULPI_CLK/ENET_RX_CLK/LCD_DCLK/SD_CLK/ADC1_1_D4") (pintype "bidirectional"))
    )
    (net (code "68") (name "/ENET_RX_DV") (class "Default")
      (node (ref "H5") (pin "14") (pinfunction "14_14") (pintype "passive"))
      (node (ref "U1") (pin "M7") (pinfunction "P1_16/GPIO0[3]/U2_RXD/SGPIO3/ENET_CRS/T0_MAT0/EMC_D9/ENET_RX_DV_M7") (pintype "bidirectional"))
    )
    (net (code "69") (name "/ENET_RX_ER") (class "Default")
      (node (ref "H5") (pin "24") (pinfunction "24_24") (pintype "passive"))
      (node (ref "U1") (pin "N6") (pinfunction "P9_1/GPIO4[13]/MCOA2/I2S0_TX_WS/ENET_RX_ER/SGPIO1/SSP0_MISO_N6") (pintype "bidirectional"))
    )
    (net (code "70") (name "/ENET_TXD0") (class "Default")
      (node (ref "H5") (pin "4") (pinfunction "4_4") (pintype "passive"))
      (node (ref "U1") (pin "N12") (pinfunction "P1_18/GPIO0[13]/U2_DIR/ENET_TXD0/T0_MAT3/CAN1_RD/SGPIO12/EMC_D10_N12") (pintype "bidirectional"))
    )
    (net (code "71") (name "/ENET_TXD1") (class "Default")
      (node (ref "H5") (pin "8") (pinfunction "8_8") (pintype "passive"))
      (node (ref "U1") (pin "M10") (pinfunction "P1_20/GPIO0[15]/SSP1_SSEL/ENET_TXD1/T0_CAP2/SGPIO13/EMC_D11_M10") (pintype "bidirectional"))
    )
    (net (code "72") (name "/ENET_TXD2") (class "Default")
      (node (ref "H5") (pin "7") (pinfunction "7_7") (pintype "passive"))
      (node (ref "U1") (pin "N10") (pinfunction "P9_4/MCOB0/USB1_IND0/GPIO5[17]/ENET_TXD2/SGPIO4/U3_RXD_N10") (pintype "bidirectional"))
    )
    (net (code "73") (name "/ENET_TXD3") (class "Default")
      (node (ref "H5") (pin "9") (pinfunction "9_9") (pintype "passive"))
      (node (ref "U1") (pin "M9") (pinfunction "P9_5/MCOA1/USB1_PPWR/GPIO5[18]/ENET_TXD3/SGPIO3/U0_TXD_M9") (pintype "bidirectional"))
    )
    (net (code "74") (name "/ENET_TX_CLK") (class "Default")
      (node (ref "H5") (pin "6") (pinfunction "6_6") (pintype "passive"))
      (node (ref "U1") (pin "M11") (pinfunction "P1_19/ENET_TX_CLK(ENET_REF_CLK)/SSP1_SCK/CLKOUT/I2S0_RX_MCLK/I2S1_TX_SCK_M11") (pintype "bidirectional"))
    )
    (net (code "75") (name "/ENET_TX_EN") (class "Default")
      (node (ref "H5") (pin "28") (pinfunction "28_28") (pintype "passive"))
      (node (ref "U1") (pin "M2") (pinfunction "P0_1/GPIO0[1]/SSP1_MOSI/ENET_COL/SGPIO1/ENET_TX_EN/I2S1_TX_SDA_M2") (pintype "bidirectional"))
    )
    (net (code "76") (name "/I2C0_SCL") (class "Default")
      (node (ref "H3") (pin "12") (pinfunction "12_12") (pintype "passive"))
      (node (ref "U1") (pin "L15") (pinfunction "I2C0_SCL_L15") (pintype "bidirectional"))
    )
    (net (code "77") (name "/I2C0_SDA") (class "Default")
      (node (ref "H3") (pin "13") (pinfunction "13_13") (pintype "passive"))
      (node (ref "U1") (pin "L16") (pinfunction "I2C0_SDA_L16") (pintype "bidirectional"))
    )
    (net (code "78") (name "/LCD_DCLK") (class "Default")
      (node (ref "H1") (pin "31") (pinfunction "31_31") (pintype "passive"))
      (node (ref "U1") (pin "H4") (pinfunction "P4_7/LCD_DCLK/GP_CLKIN/I2S1_TX_SCK/I2S0_TX_SCK_H4") (pintype "bidirectional"))
    )
    (net (code "79") (name "/LCD_EN") (class "Default")
      (node (ref "H1") (pin "32") (pinfunction "32_32") (pintype "passive"))
      (node (ref "U1") (pin "C1") (pinfunction "P4_6/GPIO2[6]/CTOUT_4/LCD_ENAB/LCDM/SGPIO12_C1") (pintype "bidirectional"))
    )
    (net (code "80") (name "/LCD_FP") (class "Default")
      (node (ref "H1") (pin "30") (pinfunction "30_30") (pintype "passive"))
      (node (ref "U1") (pin "D2") (pinfunction "P4_5/GPIO2[5]/CTOUT_5/LCD_FP/SGPIO11_D2") (pintype "bidirectional"))
    )
    (net (code "81") (name "/LCD_VD0") (class "Default")
      (node (ref "H1") (pin "28") (pinfunction "28_28") (pintype "passive"))
      (node (ref "U1") (pin "A1") (pinfunction "P4_1/GPIO2[1]/CTOUT_1/LCD_VD0/LCD_VD19/U3_TXD/ENET_COL/ADC0_1_A1") (pintype "bidirectional"))
    )
    (net (code "82") (name "/LCD_VD1") (class "Default")
      (node (ref "H1") (pin "27") (pinfunction "27_27") (pintype "passive"))
      (node (ref "U1") (pin "B1") (pinfunction "P4_4/GPIO2[4]/CTOUT_2/LCD_VD1/LCD_VD20/U3_DIR/SGPIO10/DAC_B1") (pintype "bidirectional"))
    )
    (net (code "83") (name "/LCD_VD2") (class "Default")
      (node (ref "H1") (pin "26") (pinfunction "26_26") (pintype "passive"))
      (node (ref "U1") (pin "C2") (pinfunction "P4_3/GPIO2[3]/CTOUT_3/LCD_VD2/LCD_VD21/U3_BAUD/SGPIO9/ADC0_0_C2") (pintype "bidirectional"))
    )
    (net (code "84") (name "/LCD_VD3") (class "Default")
      (node (ref "H1") (pin "25") (pinfunction "25_25") (pintype "passive"))
      (node (ref "U1") (pin "D3") (pinfunction "P4_2/GPIO2[2]/CTOUT_0/LCD_VD3/LCD_VD12/U3_RXD/SGPIO8_D3") (pintype "bidirectional"))
    )
    (net (code "85") (name "/LCD_VD4") (class "Default")
      (node (ref "H1") (pin "24") (pinfunction "24_24") (pintype "passive"))
      (node (ref "U1") (pin "K1") (pinfunction "P8_7/GPIO4[7]/USB1_ULPI_STP/LCD_VD4/LCD_PWR/T0_CAP3_K1") (pintype "bidirectional"))
    )
    (net (code "86") (name "/LCD_VD5") (class "Default")
      (node (ref "H1") (pin "23") (pinfunction "23_23") (pintype "passive"))
      (node (ref "U1") (pin "K3") (pinfunction "P8_6/GPIO4[6]/USB1_ULPI_NXT/LCD_VD5/LCD_LP/T0_CAP2_K3") (pintype "bidirectional"))
    )
    (net (code "87") (name "/LCD_VD6") (class "Default")
      (node (ref "H1") (pin "22") (pinfunction "22_22") (pintype "passive"))
      (node (ref "U1") (pin "J1") (pinfunction "P8_5/GPIO4[5]/USB1_ULPI_D0/LCD_VD6/LCD_VD8/T0_CAP1_J1") (pintype "bidirectional"))
    )
    (net (code "88") (name "/LCD_VD7") (class "Default")
      (node (ref "H1") (pin "21") (pinfunction "21_21") (pintype "passive"))
      (node (ref "U1") (pin "J2") (pinfunction "P8_4/GPIO4[4]/USB1_ULPI_D1/LCD_VD7/LCD_VD16/T0_CAP0_J2") (pintype "bidirectional"))
    )
    (net (code "89") (name "/LCD_VD8") (class "Default")
      (node (ref "H1") (pin "20") (pinfunction "20_20") (pintype "passive"))
      (node (ref "U1") (pin "A7") (pinfunction "P7_5/GPIO3[13]/CTOUT_12/LCD_VD8/LCD_VD23/TRACEDATA[1]/ADC0_3_A7") (pintype "bidirectional"))
    )
    (net (code "90") (name "/LCD_VD9") (class "Default")
      (node (ref "H1") (pin "19") (pinfunction "19_19") (pintype "passive"))
      (node (ref "U1") (pin "E2") (pinfunction "P4_8/CTIN_5/LCD_VD9/GPIO5[12]/LCD_VD22/CAN1_TD/SGPIO13_E2") (pintype "bidirectional"))
    )
    (net (code "91") (name "/LCD_VD10") (class "Default")
      (node (ref "H1") (pin "18") (pinfunction "18_18") (pintype "passive"))
      (node (ref "U1") (pin "M3") (pinfunction "P4_10/CTIN_2/LCD_VD10/GPIO5[14]/LCD_VD14/SGPIO15_M3") (pintype "bidirectional"))
    )
    (net (code "92") (name "/LCD_VD11") (class "Default")
      (node (ref "H1") (pin "17") (pinfunction "17_17") (pintype "passive"))
      (node (ref "U1") (pin "L2") (pinfunction "P4_9/CTIN_6/LCD_VD11/GPIO5[13]/LCD_VD15/CAN1_RD/SGPIO14_L2") (pintype "bidirectional"))
    )
    (net (code "93") (name "/LCD_VD12") (class "Default")
      (node (ref "H1") (pin "16") (pinfunction "16_16") (pintype "passive"))
      (node (ref "U1") (pin "J3") (pinfunction "P8_3/GPIO4[3]/USB1_ULPI_D2/LCD_VD12/LCD_VD19/T0_MAT3_J3") (pintype "bidirectional"))
    )
    (net (code "94") (name "/LCD_VD13") (class "Default")
      (node (ref "H1") (pin "15") (pinfunction "15_15") (pintype "passive"))
      (node (ref "U1") (pin "A6") (pinfunction "PB_6/USB1_ULPI_D3/LCD_VD13/GPIO5[26]/CTIN_6/LCD_VD19/ADC0_6_A6") (pintype "bidirectional"))
    )
    (net (code "95") (name "/LCD_VD14") (class "Default")
      (node (ref "H1") (pin "14") (pinfunction "14_14") (pintype "passive"))
      (node (ref "U1") (pin "A12") (pinfunction "PB_5/USB1_ULPI_D4/LCD_VD14/GPIO5[25]/CTIN_7/LCD_PWR_A12") (pintype "bidirectional"))
    )
    (net (code "96") (name "/LCD_VD15") (class "Default")
      (node (ref "H1") (pin "13") (pinfunction "13_13") (pintype "passive"))
      (node (ref "U1") (pin "B11") (pinfunction "PB_4/USB1_ULPI_D5/LCD_VD15/GPIO5[24]/CTIN_5_B11") (pintype "bidirectional"))
    )
    (net (code "97") (name "/LCD_VD16") (class "Default")
      (node (ref "H1") (pin "12") (pinfunction "12_12") (pintype "passive"))
      (node (ref "U1") (pin "C8") (pinfunction "P7_4/GPIO3[12]/CTOUT_13/LCD_VD16/LCD_VD4/TRACEDATA[0]/ADC0_4_C8") (pintype "bidirectional"))
    )
    (net (code "98") (name "/LCD_VD17") (class "Default")
      (node (ref "H1") (pin "11") (pinfunction "11_11") (pintype "passive"))
      (node (ref "U1") (pin "C13") (pinfunction "P7_3/GPIO3[11]/CTIN_3/LCD_VD17/LCD_VD5_C13") (pintype "bidirectional"))
    )
    (net (code "99") (name "/LCD_VD18") (class "Default")
      (node (ref "H1") (pin "10") (pinfunction "10_10") (pintype "passive"))
      (node (ref "U1") (pin "A16") (pinfunction "P7_2/GPIO3[10]/CTIN_4/I2S0_TX_SDA/LCD_VD18/LCD_VD6/U2_RXD/SGPIO6_A16") (pintype "bidirectional"))
    )
    (net (code "100") (name "/LCD_VD19") (class "Default")
      (node (ref "H1") (pin "9") (pinfunction "9_9") (pintype "passive"))
      (node (ref "U1") (pin "C14") (pinfunction "P7_1/GPIO3[9]/CTOUT_15/I2S0_TX_WS/LCD_VD19/LCD_VD7/U2_TXD/SGPIO5_C14") (pintype "bidirectional"))
    )
    (net (code "101") (name "/LCD_VD20") (class "Default")
      (node (ref "H1") (pin "8") (pinfunction "8_8") (pintype "passive"))
      (node (ref "U1") (pin "A13") (pinfunction "PB_3/USB1_ULPI_D6/LCD_VD20/GPIO5[23]/CTOUT_8_A13") (pintype "bidirectional"))
    )
    (net (code "102") (name "/LCD_VD21") (class "Default")
      (node (ref "H1") (pin "7") (pinfunction "7_7") (pintype "passive"))
      (node (ref "U1") (pin "B12") (pinfunction "PB_2/USB1_ULPI_D7/LCD_VD21/GPIO5[22]/CTOUT_7_B12") (pintype "bidirectional"))
    )
    (net (code "103") (name "/LCD_VD22") (class "Default")
      (node (ref "H1") (pin "6") (pinfunction "6_6") (pintype "passive"))
      (node (ref "U1") (pin "A14") (pinfunction "PB_1/USB1_ULPI_DIR/LCD_VD22/GPIO5[21]/CTOUT_6_A14") (pintype "bidirectional"))
    )
    (net (code "104") (name "/LCD_VD23") (class "Default")
      (node (ref "H1") (pin "5") (pinfunction "5_5") (pintype "passive"))
      (node (ref "U1") (pin "B15") (pinfunction "PB_0/CTOUT_10/LCD_VD23/GPIO5[20]_B15") (pintype "bidirectional"))
    )
    (net (code "105") (name "/P1_3") (class "Default")
      (node (ref "H5") (pin "25") (pinfunction "25_25") (pintype "passive"))
      (node (ref "U1") (pin "P5") (pinfunction "P1_3/GPIO0[10]/CTOUT_8/SGPIO10/~{EMC_OE}/USB0_IND1/SSP1_MISO/SD_RST_P5") (pintype "bidirectional"))
    )
    (net (code "106") (name "/P1_4") (class "Default")
      (node (ref "H5") (pin "22") (pinfunction "22_22") (pintype "passive"))
      (node (ref "U1") (pin "T3") (pinfunction "P1_4/GPIO0[11]/CTOUT_9/SGPIO11/~{EMC_BLS0}/USB0_IND0/SSP1_MOSI/EMC_D15/SD_VOLT1_T3") (pintype "bidirectional"))
    )
    (net (code "107") (name "/P1_5") (class "Default")
      (node (ref "H5") (pin "17") (pinfunction "17_17") (pintype "passive"))
      (node (ref "U1") (pin "R5") (pinfunction "P1_5/GPIO1[8]/CTOUT_10/~{EMC_CS0}/USB0_PWR_FAULT/SSP1_SSEL/SGPIO15/SD_POW_R5") (pintype "bidirectional"))
    )
    (net (code "108") (name "/P2_3") (class "Default")
      (node (ref "H4") (pin "5") (pinfunction "5_5") (pintype "passive"))
      (node (ref "U1") (pin "J12") (pinfunction "P2_3/SGPIO12/I2C1_SDA/U3_TXD/CTIN_1/GPIO5[3]/T3_MAT0/USB0_PPWR_J12") (pintype "bidirectional"))
    )
    (net (code "109") (name "/P2_4") (class "Default")
      (node (ref "H4") (pin "7") (pinfunction "7_7") (pintype "passive"))
      (node (ref "U1") (pin "K11") (pinfunction "P2_4/SGPIO13/I2C1_SCL/U3_RXD/CTIN_0/GPIO5[4]/T3_MAT1/USB0_PWR_FAULT_K11") (pintype "bidirectional"))
    )
    (net (code "110") (name "/P2_5") (class "Default")
      (node (ref "H3") (pin "15") (pinfunction "15_15") (pintype "passive"))
      (node (ref "U1") (pin "K14") (pinfunction "P2_5/SGPIO14/CTIN_2/USB1_VBUS/ADCTRIG1/GPIO5[5]/T3_MAT2/USB0_IND0_K14") (pintype "bidirectional"))
    )
    (net (code "111") (name "/P3_0") (class "Default")
      (node (ref "H3") (pin "19") (pinfunction "19_19") (pintype "passive"))
      (node (ref "U1") (pin "F13") (pinfunction "P3_0/I2S0_RX_SCK/I2S0_RX_MCLK/I2S0_TX_SCK/I2S0_TX_MCLK/SSP0_SCK_F13") (pintype "bidirectional"))
    )
    (net (code "112") (name "/P3_1") (class "Default")
      (node (ref "H3") (pin "5") (pinfunction "5_5") (pintype "passive"))
      (node (ref "U1") (pin "G11") (pinfunction "P3_1/I2S0_TX_WS/I2S0_RX_WS/CAN0_RD/USB1_IND1/GPIO5[8]/LCD_VD15_G11") (pintype "bidirectional"))
    )
    (net (code "113") (name "/P3_2") (class "Default")
      (node (ref "H2") (pin "4") (pinfunction "4_4") (pintype "passive"))
      (node (ref "U1") (pin "F11") (pinfunction "P3_2/I2S0_TX_SDA/I2S0_RX_SDA/CAN0_TD/USB1_IND0/GPIO5[9]/LCD_VD14_F11") (pintype "bidirectional"))
    )
    (net (code "114") (name "/P3_3") (class "Default")
      (node (ref "H2") (pin "5") (pinfunction "5_5") (pintype "passive"))
      (node (ref "U1") (pin "B14") (pinfunction "P3_3/SPI_SCK/SSP0_SCK/SPIFI_SCK/CGU_OUT1/I2S0_TX_MCLK/I2S1_TX_SCK_B14") (pintype "bidirectional"))
    )
    (net (code "115") (name "/P3_4") (class "Default")
      (node (ref "H3") (pin "30") (pinfunction "30_30") (pintype "passive"))
      (node (ref "U1") (pin "A15") (pinfunction "P3_4/GPIO1[14]/SPIFI_SIO3/U1_TXD/I2S0_TX_WS/I2S1_RX_SDA/LCD_VD13_A15") (pintype "bidirectional"))
    )
    (net (code "116") (name "/P3_5") (class "Default")
      (node (ref "H2") (pin "12") (pinfunction "12_12") (pintype "passive"))
      (node (ref "U1") (pin "C12") (pinfunction "P3_5/GPIO1[15]/SPIFI_SIO2/U1_RXD/I2S0_TX_SDA/I2S1_RX_WS/LCD_VD12_C12") (pintype "bidirectional"))
    )
    (net (code "117") (name "/P3_6") (class "Default")
      (node (ref "H2") (pin "9") (pinfunction "9_9") (pintype "passive"))
      (node (ref "U1") (pin "B13") (pinfunction "P3_6/GPIO0[6]/SPI_MISO/SSP0_SSEL/SPIFI_MISO/SSP0_MISO_B13") (pintype "bidirectional"))
    )
    (net (code "118") (name "/P3_7") (class "Default")
      (node (ref "H2") (pin "13") (pinfunction "13_13") (pintype "passive"))
      (node (ref "U1") (pin "C11") (pinfunction "P3_7/SPI_MOSI/SSP0_MISO/SPIFI_MOSI/GPIO5[10]/SSP0_MOSI_C11") (pintype "bidirectional"))
    )
    (net (code "119") (name "/P3_8") (class "Default")
      (node (ref "H2") (pin "15") (pinfunction "15_15") (pintype "passive"))
      (node (ref "U1") (pin "C10") (pinfunction "P3_8/SPI_SSEL/SSP0_MOSI/SPIFI_CS/GPIO5[11]/SSP0_SSEL_C10") (pintype "bidirectional"))
    )
    (net (code "120") (name "/P4_0") (class "Default")
      (node (ref "H1") (pin "54") (pinfunction "54_54") (pintype "passive"))
      (node (ref "U1") (pin "D5") (pinfunction "P4_0/GPIO2[0]/MCOA0/NMI/LCD_VD13/U3_UCLK_D5") (pintype "bidirectional"))
    )
    (net (code "121") (name "/P6_0") (class "Default")
      (node (ref "H4") (pin "29") (pinfunction "29_29") (pintype "passive"))
      (node (ref "U1") (pin "M12") (pinfunction "P6_0/I2S0_RX_MCLK/I2S0_RX_SCK_M12") (pintype "bidirectional"))
    )
    (net (code "122") (name "/P6_1") (class "Default")
      (node (ref "H4") (pin "12") (pinfunction "12_12") (pintype "passive"))
      (node (ref "U1") (pin "R15") (pinfunction "P6_1/GPIO3[0]/~{EMC_DYCS1}/U0_UCLK/I2S0_RX_WS/T2_CAP0_R15") (pintype "bidirectional"))
    )
    (net (code "123") (name "/P6_2") (class "Default")
      (node (ref "H4") (pin "9") (pinfunction "9_9") (pintype "passive"))
      (node (ref "U1") (pin "L13") (pinfunction "P6_2/GPIO3[1]/EMC_CKEOUT1/U0_DIR/I2S0_RX_SDA/T2_CAP1_L13") (pintype "bidirectional"))
    )
    (net (code "124") (name "/P6_3") (class "Default")
      (node (ref "H4") (pin "11") (pinfunction "11_11") (pintype "passive"))
      (node (ref "U1") (pin "P15") (pinfunction "P6_3/GPIO3[2]/USB0_PPWR/SGPIO4/~{EMC_CS1}/T2_CAP2_P15") (pintype "bidirectional"))
    )
    (net (code "125") (name "/P6_6") (class "Default")
      (node (ref "H3") (pin "10") (pinfunction "10_10") (pintype "passive"))
      (node (ref "U1") (pin "L14") (pinfunction "P6_6/GPIO0[5]/~{EMC_BLS1}/SGPIO5/USB0_PWR_FAULT/T2_CAP3_L14") (pintype "bidirectional"))
    )
    (net (code "126") (name "/P6_7") (class "Default")
      (node (ref "H4") (pin "4") (pinfunction "4_4") (pintype "passive"))
      (node (ref "U1") (pin "J13") (pinfunction "P6_7/EMC_A15/SGPIO6/USB0_IND1/GPIO5[15]/T2_MAT0_J13") (pintype "bidirectional"))
    )
    (net (code "127") (name "/P7_0") (class "Default")
      (node (ref "H3") (pin "28") (pinfunction "28_28") (pintype "passive"))
      (node (ref "U1") (pin "B16") (pinfunction "P7_0/GPIO3[8]/CTOUT_14/LCD_LE/SGPIO4_B16") (pintype "bidirectional"))
    )
    (net (code "128") (name "/P7_6") (class "Default")
      (node (ref "H1") (pin "37") (pinfunction "37_37") (pintype "passive"))
      (node (ref "U1") (pin "C7") (pinfunction "P7_6/GPIO3[14]/CTOUT_11/LCD_LP/TRACEDATA[2]_C7") (pintype "bidirectional"))
    )
    (net (code "129") (name "/P7_7") (class "Default")
      (node (ref "H1") (pin "41") (pinfunction "41_41") (pintype "passive"))
      (node (ref "U1") (pin "B6") (pinfunction "P7_7/GPIO3[15]/CTOUT_8/LCD_PWR/TRACEDATA[3]/ENET_MDC/SGPIO7/ADC1_6_B6") (pintype "bidirectional"))
    )
    (net (code "130") (name "/P8_0") (class "Default")
      (node (ref "H1") (pin "39") (pinfunction "39_39") (pintype "passive"))
      (node (ref "U1") (pin "E5") (pinfunction "P8_0/GPIO4[0]/USB0_PWR_FAULT/MCI2/SGPIO8/T0_MAT0_E5") (pintype "bidirectional"))
    )
    (net (code "131") (name "/P8_1") (class "Default")
      (node (ref "H1") (pin "40") (pinfunction "40_40") (pintype "passive"))
      (node (ref "U1") (pin "H5") (pinfunction "P8_1/GPIO4[1]/USB0_IND1/MCI1/SGPIO9/T0_MAT1_H5") (pintype "bidirectional"))
    )
    (net (code "132") (name "/P8_2") (class "Default")
      (node (ref "H1") (pin "42") (pinfunction "42_42") (pintype "passive"))
      (node (ref "U1") (pin "K4") (pinfunction "P8_2/GPIO4[2]/USB0_IND0/MCI0/SGPIO10/T0_MAT2_K4") (pintype "bidirectional"))
    )
    (net (code "133") (name "/PA_0") (class "Default")
      (node (ref "H4") (pin "8") (pinfunction "8_8") (pintype "passive"))
      (node (ref "U1") (pin "L12") (pinfunction "PA_0/I2S1_RX_MCLK/CGU_OUT1_L12") (pintype "bidirectional"))
    )
    (net (code "134") (name "/PA_1") (class "Default")
      (node (ref "H3") (pin "17") (pinfunction "17_17") (pintype "passive"))
      (node (ref "U1") (pin "J14") (pinfunction "PA_1/GPIO4[8]/QEI_IDX/U2_TXD_J14") (pintype "bidirectional"))
    )
    (net (code "135") (name "/PA_2") (class "Default")
      (node (ref "H3") (pin "16") (pinfunction "16_16") (pintype "passive"))
      (node (ref "U1") (pin "K15") (pinfunction "PA_2/GPIO4[9]/QEI_PHB/U2_RXD_K15") (pintype "bidirectional"))
    )
    (net (code "136") (name "/PA_3") (class "Default")
      (node (ref "H4") (pin "3") (pinfunction "3_3") (pintype "passive"))
      (node (ref "U1") (pin "H11") (pinfunction "PA_3/GPIO4[10]/QEI_PHA_H11") (pintype "bidirectional"))
    )
    (net (code "137") (name "/PA_4") (class "Default")
      (node (ref "H3") (pin "6") (pinfunction "6_6") (pintype "passive"))
      (node (ref "U1") (pin "G13") (pinfunction "PA_4/CTOUT_9/EMC_A23/GPIO5[19]_G13") (pintype "bidirectional"))
    )
    (net (code "138") (name "/PC_13") (class "Default")
      (node (ref "H5") (pin "29") (pinfunction "29_29") (pintype "passive"))
      (node (ref "U1") (pin "M1") (pinfunction "PC_13/U1_TXD/GPIO6[12]/SGPIO12/I2S0_TX_WS/SD_DAT6_M1") (pintype "bidirectional"))
    )
    (net (code "139") (name "/PC_14") (class "Default")
      (node (ref "H1") (pin "60") (pinfunction "60_60") (pintype "passive"))
      (node (ref "U1") (pin "N1") (pinfunction "PC_14/U1_RXD/GPIO6[13]/SGPIO13/ENET_TX_ER/SD_DAT7_N1") (pintype "bidirectional"))
    )
    (net (code "140") (name "/PD_0") (class "Default")
      (node (ref "H1") (pin "53") (pinfunction "53_53") (pintype "passive"))
      (node (ref "U1") (pin "N2") (pinfunction "PD_0/CTOUT_15/EMC_DQMOUT2/GPIO6[14]/SGPIO4_N2") (pintype "bidirectional"))
    )
    (net (code "141") (name "/PD_1") (class "Default")
      (node (ref "H1") (pin "55") (pinfunction "55_55") (pintype "passive"))
      (node (ref "U1") (pin "P1") (pinfunction "PD_1/EMC_CKEOUT2/GPIO6[15]/SD_POW/SGPIO5_P1") (pintype "bidirectional"))
    )
    (net (code "142") (name "/PD_2") (class "Default")
      (node (ref "H5") (pin "26") (pinfunction "26_26") (pintype "passive"))
      (node (ref "U1") (pin "R1") (pinfunction "PD_2/CTOUT_7/EMC_D16/GPIO6[16]/SGPIO6_R1") (pintype "bidirectional"))
    )
    (net (code "143") (name "/PD_3") (class "Default")
      (node (ref "H5") (pin "23") (pinfunction "23_23") (pintype "passive"))
      (node (ref "U1") (pin "P4") (pinfunction "PD_3/CTOUT_6/EMC_D17/GPIO6[17]/SGPIO7_P4") (pintype "bidirectional"))
    )
    (net (code "144") (name "/PD_8") (class "Default")
      (node (ref "H5") (pin "12") (pinfunction "12_12") (pintype "passive"))
      (node (ref "U1") (pin "P8") (pinfunction "PD_8/CTIN_6/EMC_D22/GPIO6[22]/SGPIO12_P8") (pintype "bidirectional"))
    )
    (net (code "145") (name "/PD_9") (class "Default")
      (node (ref "H4") (pin "23") (pinfunction "23_23") (pintype "passive"))
      (node (ref "U1") (pin "T11") (pinfunction "PD_9/CTOUT_13/EMC_D23/GPIO6[23]/SGPIO13_T11") (pintype "bidirectional"))
    )
    (net (code "146") (name "/PD_10") (class "Default")
      (node (ref "H4") (pin "22") (pinfunction "22_22") (pintype "passive"))
      (node (ref "U1") (pin "P11") (pinfunction "PD_10/CTIN_1/~{EMC_BLS3}/GPIO6[24]_P11") (pintype "bidirectional"))
    )
    (net (code "147") (name "/PD_11") (class "Default")
      (node (ref "H5") (pin "10") (pinfunction "10_10") (pintype "passive"))
      (node (ref "U1") (pin "N9") (pinfunction "PD_11/~{EMC_CS3}/GPIO6[25]/USB1_ULPI_D0/CTOUT_14_N9") (pintype "bidirectional"))
    )
    (net (code "148") (name "/PD_12") (class "Default")
      (node (ref "H4") (pin "30") (pinfunction "30_30") (pintype "passive"))
      (node (ref "U1") (pin "N11") (pinfunction "PD_12/~{EMC_CS2}/GPIO6[26]/CTOUT_10_N11") (pintype "bidirectional"))
    )
    (net (code "149") (name "/PD_13") (class "Default")
      (node (ref "H4") (pin "16") (pinfunction "16_16") (pintype "passive"))
      (node (ref "U1") (pin "T14") (pinfunction "PD_13/CTIN_0/~{EMC_BLS2}/GPIO6[27]/CTOUT_13_T14") (pintype "bidirectional"))
    )
    (net (code "150") (name "/PD_14") (class "Default")
      (node (ref "H4") (pin "18") (pinfunction "18_18") (pintype "passive"))
      (node (ref "U1") (pin "R13") (pinfunction "PD_14/~{EMC_DYCS2}/GPIO6[28]/CTOUT_11_R13") (pintype "bidirectional"))
    )
    (net (code "151") (name "/PD_15") (class "Default")
      (node (ref "H4") (pin "14") (pinfunction "14_14") (pintype "passive"))
      (node (ref "U1") (pin "T15") (pinfunction "PD_15/EMC_A17/GPIO6[29]/SD_WP/CTOUT_8_T15") (pintype "bidirectional"))
    )
    (net (code "152") (name "/PD_16") (class "Default")
      (node (ref "H4") (pin "15") (pinfunction "15_15") (pintype "passive"))
      (node (ref "U1") (pin "R14") (pinfunction "PD_16/EMC_A16/GPIO6[30]/SD_VOLT2/CTOUT_12_R14") (pintype "bidirectional"))
    )
    (net (code "153") (name "/PE_0") (class "Default")
      (node (ref "H4") (pin "13") (pinfunction "13_13") (pintype "passive"))
      (node (ref "U1") (pin "P14") (pinfunction "PE_0/EMC_A18/GPIO7[0]/CAN1_TD_P14") (pintype "bidirectional"))
    )
    (net (code "154") (name "/PE_1") (class "Default")
      (node (ref "H4") (pin "10") (pinfunction "10_10") (pintype "passive"))
      (node (ref "U1") (pin "N14") (pinfunction "PE_1/EMC_A19/GPIO7[1]/CAN1_RD_N14") (pintype "bidirectional"))
    )
    (net (code "155") (name "/PE_2") (class "Default")
      (node (ref "H3") (pin "8") (pinfunction "8_8") (pintype "passive"))
      (node (ref "U1") (pin "M14") (pinfunction "PE_2/ADCTRIG0/CAN0_RD/EMC_A20/GPIO7[2]_M14") (pintype "bidirectional"))
    )
    (net (code "156") (name "/PE_3") (class "Default")
      (node (ref "H4") (pin "6") (pinfunction "6_6") (pintype "passive"))
      (node (ref "U1") (pin "K12") (pinfunction "PE_3/CAN0_TD/ADCTRIG1/EMC_A21/GPIO7[3]_K12") (pintype "bidirectional"))
    )
    (net (code "157") (name "/PE_4") (class "Default")
      (node (ref "H3") (pin "14") (pinfunction "14_14") (pintype "passive"))
      (node (ref "U1") (pin "K13") (pinfunction "PE_4/NMI/EMC_A22/GPIO7[4]_K13") (pintype "bidirectional"))
    )
    (net (code "158") (name "/PE_5") (class "Default")
      (node (ref "H3") (pin "7") (pinfunction "7_7") (pintype "passive"))
      (node (ref "U1") (pin "N16") (pinfunction "PE_5/CTOUT_3/U1_RTS/EMC_D24/GPIO7[5]_N16") (pintype "bidirectional"))
    )
    (net (code "159") (name "/PE_6") (class "Default")
      (node (ref "H3") (pin "11") (pinfunction "11_11") (pintype "passive"))
      (node (ref "U1") (pin "M16") (pinfunction "PE_6/CTOUT_2/U1_RI/EMC_D25/GPIO7[6]_M16") (pintype "bidirectional"))
    )
    (net (code "160") (name "/PE_7") (class "Default")
      (node (ref "H3") (pin "20") (pinfunction "20_20") (pintype "passive"))
      (node (ref "U1") (pin "F15") (pinfunction "PE_7/CTOUT_5/U1_CTS/EMC_D26/GPIO7[7]_F15") (pintype "bidirectional"))
    )
    (net (code "161") (name "/PE_8") (class "Default")
      (node (ref "H3") (pin "21") (pinfunction "21_21") (pintype "passive"))
      (node (ref "U1") (pin "F14") (pinfunction "PE_8/CTOUT_4/U1_DSR/EMC_D27/GPIO7[8]_F14") (pintype "bidirectional"))
    )
    (net (code "162") (name "/PE_9") (class "Default")
      (node (ref "H3") (pin "22") (pinfunction "22_22") (pintype "passive"))
      (node (ref "U1") (pin "E16") (pinfunction "PE_9/CTIN_4/U1_DCD/EMC_D28/GPIO7[9]_E16") (pintype "bidirectional"))
    )
    (net (code "163") (name "/PE_10") (class "Default")
      (node (ref "H3") (pin "24") (pinfunction "24_24") (pintype "passive"))
      (node (ref "U1") (pin "E14") (pinfunction "PE_10/CTIN_3/U1_DTR/EMC_D29/GPIO7[10]_E14") (pintype "bidirectional"))
    )
    (net (code "164") (name "/PE_11") (class "Default")
      (node (ref "H3") (pin "25") (pinfunction "25_25") (pintype "passive"))
      (node (ref "U1") (pin "D16") (pinfunction "PE_11/CTOUT_12/U1_TXD/EMC_D30/GPIO7[11]_D16") (pintype "bidirectional"))
    )
    (net (code "165") (name "/PE_12") (class "Default")
      (node (ref "H3") (pin "26") (pinfunction "26_26") (pintype "passive"))
      (node (ref "U1") (pin "D15") (pinfunction "PE_12/CTOUT_11/U1_RXD/EMC_D31/GPIO7[12]_D15") (pintype "bidirectional"))
    )
    (net (code "166") (name "/PE_13") (class "Default")
      (node (ref "H3") (pin "18") (pinfunction "18_18") (pintype "passive"))
      (node (ref "U1") (pin "G14") (pinfunction "PE_13/CTOUT_14/I2C1_SDA/EMC_DQMOUT3/GPIO7[13]_G14") (pintype "bidirectional"))
    )
    (net (code "167") (name "/PE_14") (class "Default")
      (node (ref "H3") (pin "29") (pinfunction "29_29") (pintype "passive"))
      (node (ref "U1") (pin "C15") (pinfunction "PE_14/~{EMC_DYCS3}/GPIO7[14]_C15") (pintype "bidirectional"))
    )
    (net (code "168") (name "/PE_15") (class "Default")
      (node (ref "H3") (pin "23") (pinfunction "23_23") (pintype "passive"))
      (node (ref "U1") (pin "E13") (pinfunction "PE_15/CTOUT_0/I2C1_SCL/EMC_CKEOUT3/GPIO7[15]_E13") (pintype "bidirectional"))
    )
    (net (code "169") (name "/PF_0") (class "Default")
      (node (ref "H2") (pin "8") (pinfunction "8_8") (pintype "passive"))
      (node (ref "U1") (pin "D12") (pinfunction "PF_0/SSP0_SCK/GP_CLKIN/I2S1_TX_MCLK_D12") (pintype "bidirectional"))
    )
    (net (code "170") (name "/PF_1") (class "Default")
      (node (ref "H2") (pin "7") (pinfunction "7_7") (pintype "passive"))
      (node (ref "U1") (pin "E11") (pinfunction "PF_1/SSP0_SSEL/GPIO7[16]/SGPIO0_E11") (pintype "bidirectional"))
    )
    (net (code "171") (name "/PF_2") (class "Default")
      (node (ref "H2") (pin "10") (pinfunction "10_10") (pintype "passive"))
      (node (ref "U1") (pin "D11") (pinfunction "PF_2/U3_TXD/SSP0_MISO/GPIO7[17]/SGPIO1_D11") (pintype "bidirectional"))
    )
    (net (code "172") (name "/PF_3") (class "Default")
      (node (ref "H2") (pin "3") (pinfunction "3_3") (pintype "passive"))
      (node (ref "U1") (pin "E10") (pinfunction "PF_3/U3_RXD/SSP0_MOSI/GPIO7[18]/SGPIO2_E10") (pintype "bidirectional"))
    )
    (net (code "173") (name "/PF_4") (class "Default")
      (node (ref "H2") (pin "16") (pinfunction "16_16") (pintype "passive"))
      (node (ref "U1") (pin "D10") (pinfunction "PF_4/SSP1_SCK/GP_CLKIN/TRACECLK/I2S0_TX_MCLK/I2S0_RX_SCK_D10") (pintype "bidirectional"))
    )
    (net (code "174") (name "/PF_5") (class "Default")
      (node (ref "H2") (pin "6") (pinfunction "6_6") (pintype "passive"))
      (node (ref "U1") (pin "E9") (pinfunction "PF_5/U3_UCLK/SSP1_SSEL/TRACEDATA[0]/GPIO7[19]/SGPIO4/ADC1_4_E9") (pintype "bidirectional"))
    )
    (net (code "175") (name "/PF_6") (class "Default")
      (node (ref "H1") (pin "36") (pinfunction "36_36") (pintype "passive"))
      (node (ref "U1") (pin "E7") (pinfunction "PF_6/U3_DIR/SSP1_MISO/TRACEDATA[1]/GPIO7[20]/SGPIO5/I2S1_TX_SDA/ADC1_3_E7") (pintype "bidirectional"))
    )
    (net (code "176") (name "/PF_7") (class "Default")
      (node (ref "H1") (pin "38") (pinfunction "38_38") (pintype "passive"))
      (node (ref "U1") (pin "B7") (pinfunction "PF_7/U3_BAUD/SSP1_MOSI/TRACEDATA[2]/GPIO7[21]/SGPIO6/I2S1_TX_WS/ADC1_7_B7") (pintype "bidirectional"))
    )
    (net (code "177") (name "/PF_8") (class "Default")
      (node (ref "H1") (pin "44") (pinfunction "44_44") (pintype "passive"))
      (node (ref "U1") (pin "E6") (pinfunction "PF_8/U0_UCLK/CTIN_2/TRACEDATA[3]/GPIO7[22]/SGPIO7/ADC0_2_E6") (pintype "bidirectional"))
    )
    (net (code "178") (name "/PF_9") (class "Default")
      (node (ref "H1") (pin "47") (pinfunction "47_47") (pintype "passive"))
      (node (ref "U1") (pin "D6") (pinfunction "PF_9/U0_DIR/CTOUT_1/GPIO7[23]/SGPIO3/ADC1_2_D6") (pintype "bidirectional"))
    )
    (net (code "179") (name "/PF_10") (class "Default")
      (node (ref "H1") (pin "51") (pinfunction "51_51") (pintype "passive"))
      (node (ref "U1") (pin "A3") (pinfunction "PF_10/U0_TXD/GPIO7[24]/SD_WP/ADC0_5_A3") (pintype "bidirectional"))
    )
    (net (code "180") (name "/PF_11") (class "Default")
      (node (ref "H1") (pin "57") (pinfunction "57_57") (pintype "passive"))
      (node (ref "U1") (pin "A2") (pinfunction "PF_11/U0_RXD/GPIO7[25]/SD_VOLT2/ADC1_5_A2") (pintype "bidirectional"))
    )
    (net (code "181") (name "/REFCLK") (class "Default")
      (node (ref "C34") (pin "1") (pinfunction "1_1") (pintype "passive"))
      (node (ref "R2") (pin "2") (pinfunction "2_2") (pintype "passive"))
      (node (ref "U3") (pin "21") (pinfunction "REFCLK/XI_21") (pintype "input"))
      (node (ref "X2") (pin "3") (pinfunction "3_3") (pintype "passive"))
    )
    (net (code "182") (name "/RESET") (class "Default")
      (node (ref "C36") (pin "1") (pinfunction "1_1") (pintype "passive"))
      (node (ref "H6") (pin "10") (pinfunction "RST_10") (pintype "passive"))
      (node (ref "R8") (pin "1") (pinfunction "1_1") (pintype "passive"))
      (node (ref "S1") (pin "2") (pinfunction "2_2") (pintype "passive"))
      (node (ref "U1") (pin "D9") (pinfunction "~{RESET}_D9") (pintype "input"))
    )
    (net (code "183") (name "/RTCX1") (class "Default")
      (node (ref "H2") (pin "19") (pinfunction "19_19") (pintype "passive"))
      (node (ref "U1") (pin "A8") (pinfunction "RTCX1_A8") (pintype "passive"))
    )
    (net (code "184") (name "/RTCX2") (class "Default")
      (node (ref "H2") (pin "20") (pinfunction "20_20") (pintype "passive"))
      (node (ref "U1") (pin "B8") (pinfunction "RTCX2_B8") (pintype "passive"))
    )
    (net (code "185") (name "/RTC_ALARM") (class "Default")
      (node (ref "H2") (pin "11") (pinfunction "11_11") (pintype "passive"))
      (node (ref "U1") (pin "A11") (pinfunction "RTC_ALARM_A11") (pintype "output"))
    )
    (net (code "186") (name "/SAMPLE") (class "Default")
      (node (ref "H2") (pin "18") (pinfunction "18_18") (pintype "passive"))
      (node (ref "U1") (pin "B9") (pinfunction "~{SAMPLE}_B9") (pintype "passive"))
    )
    (net (code "187") (name "/TCK") (class "Default")
      (node (ref "H6") (pin "4") (pinfunction "TCK_4") (pintype "output"))
      (node (ref "R7") (pin "2") (pinfunction "2_2") (pintype "passive"))
      (node (ref "U1") (pin "J5") (pinfunction "TCK/SWDCLK_J5") (pintype "input"))
    )
    (net (code "188") (name "/TDI") (class "Default")
      (node (ref "H6") (pin "8") (pinfunction "TDI_8") (pintype "output"))
      (node (ref "R3") (pin "1") (pinfunction "1_1") (pintype "passive"))
      (node (ref "U1") (pin "J4") (pinfunction "TDI_J4") (pintype "input"))
    )
    (net (code "189") (name "/TDO") (class "Default")
      (node (ref "H6") (pin "6") (pinfunction "TDO_6") (pintype "passive"))
      (node (ref "R4") (pin "1") (pinfunction "1_1") (pintype "passive"))
      (node (ref "U1") (pin "K5") (pinfunction "TDO/SWO_K5") (pintype "output"))
    )
    (net (code "190") (name "/TMS") (class "Default")
      (node (ref "H6") (pin "2") (pinfunction "TMS_2") (pintype "passive"))
      (node (ref "R5") (pin "1") (pinfunction "1_1") (pintype "passive"))
      (node (ref "U1") (pin "K6") (pinfunction "TMS/SWDIO_K6") (pintype "bidirectional"))
    )
    (net (code "191") (name "/TRST") (class "Default")
      (node (ref "R6") (pin "1") (pinfunction "1_1") (pintype "passive"))
      (node (ref "TP1") (pin "1") (pintype "output"))
      (node (ref "U1") (pin "M4") (pinfunction "~{TRST}_M4") (pintype "input"))
    )
    (net (code "192") (name "/ULPI_CLKOUT") (class "Default")
      (node (ref "U1") (pin "L1") (pinfunction "P8_8/USB1_ULPI_CLK/CGU_OUT0/I2S1_TX_MCLK_L1") (pintype "bidirectional"))
      (node (ref "U3") (pin "2") (pinfunction "CLKOUT_2") (pintype "tri_state"))
    )
    (net (code "193") (name "/ULPI_D0") (class "Default")
      (node (ref "U1") (pin "N4") (pinfunction "PC_8/USB1_ULPI_D0/ENET_RX_DV/GPIO6[7]/T3_MAT1/SD_CD_N4") (pintype "bidirectional"))
      (node (ref "U3") (pin "4") (pinfunction "DATA[0]_4") (pintype "bidirectional"))
    )
    (net (code "194") (name "/ULPI_D1") (class "Default")
      (node (ref "U1") (pin "G5") (pinfunction "PC_7/USB1_ULPI_D1/ENET_RXD3/GPIO6[6]/T3_MAT0/SD_DAT3_G5") (pintype "bidirectional"))
      (node (ref "U3") (pin "5") (pinfunction "DATA[1]_5") (pintype "bidirectional"))
    )
    (net (code "195") (name "/ULPI_D2") (class "Default")
      (node (ref "U1") (pin "H6") (pinfunction "PC_6/USB1_ULPI_D2/ENET_RXD2/GPIO6[5]/T3_CAP3/SD_DAT2_H6") (pintype "bidirectional"))
      (node (ref "U3") (pin "6") (pinfunction "DATA[2]_6") (pintype "bidirectional"))
    )
    (net (code "196") (name "/ULPI_D3") (class "Default")
      (node (ref "U1") (pin "G4") (pinfunction "PC_5/USB1_ULPI_D3/ENET_TX_ER/GPIO6[4]/T3_CAP2/SD_DAT1_G4") (pintype "bidirectional"))
      (node (ref "U3") (pin "7") (pinfunction "DATA[3]_7") (pintype "bidirectional"))
    )
    (net (code "197") (name "/ULPI_D4") (class "Default")
      (node (ref "U1") (pin "F4") (pinfunction "PC_4/USB1_ULPI_D4/ENET_TX_EN/GPIO6[3]/T3_CAP1/SD_DAT0_F4") (pintype "bidirectional"))
      (node (ref "U3") (pin "8") (pinfunction "DATA[4]_8") (pintype "bidirectional"))
    )
    (net (code "198") (name "/ULPI_D5") (class "Default")
      (node (ref "U1") (pin "F5") (pinfunction "PC_3/USB1_ULPI_D5/U1_RTS/ENET_TXD3/GPIO6[2]/SD_VOLT1/ADC1_0_F5") (pintype "bidirectional"))
      (node (ref "U3") (pin "10") (pinfunction "DATA[5]_10") (pintype "bidirectional"))
    )
    (net (code "199") (name "/ULPI_D6") (class "Default")
      (node (ref "U1") (pin "F6") (pinfunction "PC_2/USB1_ULPI_D6/U1_CTS/ENET_TXD2/GPIO6[1]/SD_RST_F6") (pintype "bidirectional"))
      (node (ref "U3") (pin "11") (pinfunction "DATA[6]_11") (pintype "bidirectional"))
    )
    (net (code "200") (name "/ULPI_D7") (class "Default")
      (node (ref "U1") (pin "E4") (pinfunction "PC_1/USB1_ULPI_D7/U1_RI/ENET_MDC/GPIO6[0]/T3_CAP0/SD_VOLT0_E4") (pintype "bidirectional"))
      (node (ref "U3") (pin "12") (pinfunction "DATA[7]_12") (pintype "bidirectional"))
    )
    (net (code "201") (name "/ULPI_DIR") (class "Default")
      (node (ref "U1") (pin "L5") (pinfunction "PC_11/USB1_ULPI_DIR/U1_DCD/GPIO6[10]/SD_DAT4_L5") (pintype "bidirectional"))
      (node (ref "U3") (pin "1") (pinfunction "DIR_1") (pintype "tri_state"))
    )
    (net (code "202") (name "/ULPI_NXT") (class "Default")
      (node (ref "U1") (pin "K2") (pinfunction "PC_9/USB1_ULPI_NXT/ENET_RX_ER/GPIO6[8]/T3_MAT2/SD_POW_K2") (pintype "bidirectional"))
      (node (ref "U3") (pin "3") (pinfunction "NXT_3") (pintype "output"))
    )
    (net (code "203") (name "/ULPI_RESET") (class "Default")
      (node (ref "U1") (pin "L6") (pinfunction "PC_12/U1_DTR/GPIO6[11]/SGPIO11/I2S0_TX_SDA/SD_DAT5_L6") (pintype "bidirectional"))
      (node (ref "U3") (pin "22") (pinfunction "RESETB_22") (pintype "input"))
    )
    (net (code "204") (name "/ULPI_STP") (class "Default")
      (node (ref "U1") (pin "M5") (pinfunction "PC_10/USB1_ULPI_STP/U1_DSR/GPIO6[9]/T3_MAT3/SD_CMD_M5") (pintype "bidirectional"))
      (node (ref "U3") (pin "24") (pinfunction "STP_24") (pintype "input"))
    )
    (net (code "205") (name "/USB0_D_N") (class "Default")
      (node (ref "J2") (pin "2") (pinfunction "SIG-_2") (pintype "passive"))
      (node (ref "U1") (pin "G2") (pinfunction "USB0_DM_G2") (pintype "bidirectional"))
    )
    (net (code "206") (name "/USB0_D_P") (class "Default")
      (node (ref "J2") (pin "3") (pinfunction "SIG+_3") (pintype "passive"))
      (node (ref "U1") (pin "F2") (pinfunction "USB0_DP_F2") (pintype "bidirectional"))
    )
    (net (code "207") (name "/USB0_ID") (class "Default")
      (node (ref "J2") (pin "4") (pintype "output"))
      (node (ref "U1") (pin "H2") (pinfunction "USB0_ID_H2") (pintype "input"))
    )
    (net (code "208") (name "/USB1_DM") (class "Default")
      (node (ref "U1") (pin "G12") (pinfunction "USB1_DM_G12") (pintype "bidirectional+no_connect"))
    )
    (net (code "209") (name "/USB1_DP") (class "Default")
      (node (ref "U1") (pin "F12") (pinfunction "USB1_DP_F12") (pintype "bidirectional+no_connect"))
    )
    (net (code "210") (name "/VBUS") (class "Default")
      (node (ref "R12") (pin "2") (pinfunction "2_2") (pintype "passive"))
      (node (ref "U3") (pin "17") (pinfunction "VBUS_17") (pintype "power_in"))
    )
    (net (code "211") (name "/WAKEUP0") (class "Default")
      (node (ref "H2") (pin "17") (pinfunction "17_17") (pintype "output"))
      (node (ref "U1") (pin "A9") (pinfunction "WAKEUP0_A9") (pintype "input"))
    )
    (net (code "212") (name "/WAKEUP1") (class "Default")
      (node (ref "H2") (pin "14") (pinfunction "14_14") (pintype "output"))
      (node (ref "U1") (pin "A10") (pinfunction "WAKEUP1_A10") (pintype "input"))
    )
    (net (code "213") (name "/WAKEUP2") (class "Default")
      (node (ref "H1") (pin "34") (pinfunction "34_34") (pintype "output"))
      (node (ref "U1") (pin "C9") (pinfunction "WAKEUP2_C9") (pintype "input"))
    )
    (net (code "214") (name "/WAKEUP3") (class "Default")
      (node (ref "H1") (pin "35") (pinfunction "35_35") (pintype "output"))
      (node (ref "U1") (pin "D8") (pinfunction "WAKEUP3_D8") (pintype "input"))
    )
    (net (code "215") (name "/XO") (class "Default")
      (node (ref "C35") (pin "1") (pinfunction "1_1") (pintype "passive"))
      (node (ref "R2") (pin "1") (pinfunction "1_1") (pintype "passive"))
      (node (ref "U3") (pin "20") (pinfunction "XO_20") (pintype "passive"))
      (node (ref "X2") (pin "1") (pinfunction "1_1") (pintype "passive"))
    )
    (net (code "216") (name "/XTAL1") (class "Default")
      (node (ref "C38") (pin "1") (pinfunction "1_1") (pintype "passive"))
      (node (ref "R9") (pin "1") (pinfunction "1_1") (pintype "passive"))
      (node (ref "U1") (pin "D1") (pinfunction "XTAL1_D1") (pintype "passive"))
      (node (ref "X1") (pin "1") (pinfunction "1_1") (pintype "passive"))
    )
    (net (code "217") (name "/XTAL2") (class "Default")
      (node (ref "C37") (pin "1") (pinfunction "1_1") (pintype "passive"))
      (node (ref "R9") (pin "2") (pinfunction "2_2") (pintype "passive"))
      (node (ref "U1") (pin "E1") (pinfunction "XTAL2_E1") (pintype "passive"))
      (node (ref "X1") (pin "3") (pinfunction "3_3") (pintype "passive"))
    )
    (net (code "218") (name "3V3") (class "Default")
      (node (ref "C1") (pin "1") (pinfunction "1_1") (pintype "passive"))
      (node (ref "C10") (pin "1") (pinfunction "1_1") (pintype "passive"))
      (node (ref "C11") (pin "1") (pinfunction "1_1") (pintype "passive"))
      (node (ref "C12") (pin "1") (pinfunction "1_1") (pintype "passive"))
      (node (ref "C13") (pin "1") (pinfunction "1_1") (pintype "passive"))
      (node (ref "C14") (pin "1") (pinfunction "1_1") (pintype "passive"))
      (node (ref "C15") (pin "1") (pinfunction "1_1") (pintype "passive"))
      (node (ref "C16") (pin "1") (pinfunction "1_1") (pintype "passive"))
      (node (ref "C17") (pin "1") (pinfunction "1_1") (pintype "passive"))
      (node (ref "C18") (pin "1") (pinfunction "1_1") (pintype "passive"))
      (node (ref "C19") (pin "1") (pinfunction "1_1") (pintype "passive"))
      (node (ref "C2") (pin "1") (pinfunction "1_1") (pintype "passive"))
      (node (ref "C20") (pin "1") (pinfunction "1_1") (pintype "passive"))
      (node (ref "C21") (pin "1") (pinfunction "1_1") (pintype "passive"))
      (node (ref "C3") (pin "1") (pinfunction "1_1") (pintype "passive"))
      (node (ref "C4") (pin "1") (pinfunction "1_1") (pintype "passive"))
      (node (ref "C40") (pin "1") (pinfunction "1_1") (pintype "passive"))
      (node (ref "C5") (pin "1") (pinfunction "1_1") (pintype "passive"))
      (node (ref "C6") (pin "1") (pinfunction "1_1") (pintype "passive"))
      (node (ref "C7") (pin "1") (pinfunction "1_1") (pintype "passive"))
      (node (ref "C8") (pin "1") (pinfunction "1_1") (pintype "passive"))
      (node (ref "C9") (pin "1") (pinfunction "1_1") (pintype "passive"))
      (node (ref "D2") (pin "1") (pinfunction "ANODE_1") (pintype "passive"))
      (node (ref "FB2") (pin "1") (pinfunction "1_1") (pintype "passive"))
      (node (ref "FB4") (pin "2") (pinfunction "2_2") (pintype "passive"))
      (node (ref "FB5") (pin "2") (pinfunction "2_2") (pintype "passive"))
      (node (ref "FB6") (pin "1") (pinfunction "1_1") (pintype "passive"))
      (node (ref "FB7") (pin "1") (pinfunction "1_1") (pintype "passive"))
      (node (ref "H1") (pin "2") (pinfunction "2_2") (pintype "passive"))
      (node (ref "H2") (pin "2") (pinfunction "2_2") (pintype "passive"))
      (node (ref "H3") (pin "2") (pinfunction "2_2") (pintype "passive"))
      (node (ref "H4") (pin "2") (pinfunction "2_2") (pintype "passive"))
      (node (ref "H5") (pin "2") (pinfunction "2_2") (pintype "passive"))
      (node (ref "H6") (pin "1") (pinfunction "Vcc_1") (pintype "passive"))
      (node (ref "R13") (pin "2") (pinfunction "2_2") (pintype "passive"))
      (node (ref "R14") (pin "2") (pinfunction "2_2") (pintype "passive"))
      (node (ref "R3") (pin "2") (pinfunction "2_2") (pintype "passive"))
      (node (ref "R4") (pin "2") (pinfunction "2_2") (pintype "passive"))
      (node (ref "R5") (pin "2") (pinfunction "2_2") (pintype "passive"))
      (node (ref "R6") (pin "2") (pinfunction "2_2") (pintype "passive"))
      (node (ref "R8") (pin "2") (pinfunction "2_2") (pintype "passive"))
      (node (ref "U1") (pin "B10") (pinfunction "VBAT_B10") (pintype "power_in"))
      (node (ref "U1") (pin "D7") (pinfunction "VDDIO_D7") (pintype "power_in"))
      (node (ref "U1") (pin "E12") (pinfunction "VDDIO_E12") (pintype "power_in"))
      (node (ref "U1") (pin "E8") (pinfunction "VPP_E8") (pintype "power_in"))
      (node (ref "U1") (pin "F10") (pinfunction "VDDREG_F10") (pintype "power_in"))
      (node (ref "U1") (pin "F3") (pinfunction "USB0_VDDA3V3_DRIVER_F3") (pintype "power_in"))
      (node (ref "U1") (pin "F7") (pinfunction "VDDIO_F7") (pintype "power_in"))
      (node (ref "U1") (pin "F8") (pinfunction "VDDIO_F8") (pintype "power_in"))
      (node (ref "U1") (pin "F9") (pinfunction "VDDREG_F9") (pintype "power_in"))
      (node (ref "U1") (pin "G10") (pinfunction "VDDIO_G10") (pintype "power_in"))
      (node (ref "U1") (pin "G3") (pinfunction "USB0_VDDA3V3_G3") (pintype "power_in"))
      (node (ref "U1") (pin "H10") (pinfunction "VDDIO_H10") (pintype "power_in"))
      (node (ref "U1") (pin "J6") (pinfunction "VDDIO_J6") (pintype "power_in"))
      (node (ref "U1") (pin "J7") (pinfunction "VDDIO_J7") (pintype "power_in"))
      (node (ref "U1") (pin "K7") (pinfunction "VDDIO_K7") (pintype "power_in"))
      (node (ref "U1") (pin "L10") (pinfunction "VDDIO_L10") (pintype "power_in"))
      (node (ref "U1") (pin "L7") (pinfunction "VDDREG_L7") (pintype "power_in"))
      (node (ref "U1") (pin "L8") (pinfunction "VDDREG_L8") (pintype "power_in"))
      (node (ref "U1") (pin "L9") (pinfunction "VDDIO_L9") (pintype "power_in"))
      (node (ref "U1") (pin "N13") (pinfunction "VDDIO_N13") (pintype "power_in"))
      (node (ref "U1") (pin "N7") (pinfunction "VDDIO_N7") (pintype "power_in"))
      (node (ref "U4") (pin "2") (pinfunction "Vout_2") (pintype "power_in"))
      (node (ref "U5") (pin "2") (pinfunction "VIN_2") (pintype "power_in"))
    )
    (net (code "219") (name "GND") (class "Default")
      (node (ref "C1") (pin "2") (pinfunction "2_2") (pintype "passive"))
      (node (ref "C10") (pin "2") (pinfunction "2_2") (pintype "passive"))
      (node (ref "C11") (pin "2") (pinfunction "2_2") (pintype "passive"))
      (node (ref "C12") (pin "2") (pinfunction "2_2") (pintype "passive"))
      (node (ref "C13") (pin "2") (pinfunction "2_2") (pintype "passive"))
      (node (ref "C14") (pin "2") (pinfunction "2_2") (pintype "passive"))
      (node (ref "C15") (pin "2") (pinfunction "2_2") (pintype "passive"))
      (node (ref "C16") (pin "2") (pinfunction "2_2") (pintype "passive"))
      (node (ref "C17") (pin "2") (pinfunction "2_2") (pintype "passive"))
      (node (ref "C18") (pin "2") (pinfunction "2_2") (pintype "passive"))
      (node (ref "C19") (pin "2") (pinfunction "2_2") (pintype "passive"))
      (node (ref "C2") (pin "2") (pinfunction "2_2") (pintype "passive"))
      (node (ref "C20") (pin "2") (pinfunction "2_2") (pintype "passive"))
      (node (ref "C21") (pin "2") (pinfunction "2_2") (pintype "passive"))
      (node (ref "C22") (pin "2") (pinfunction "2_2") (pintype "passive"))
      (node (ref "C23") (pin "2") (pinfunction "2_2") (pintype "passive"))
      (node (ref "C24") (pin "2") (pinfunction "2_2") (pintype "passive"))
      (node (ref "C25") (pin "2") (pinfunction "2_2") (pintype "passive"))
      (node (ref "C26") (pin "2") (pinfunction "2_2") (pintype "passive"))
      (node (ref "C27") (pin "2") (pinfunction "2_2") (pintype "passive"))
      (node (ref "C28") (pin "2") (pinfunction "2_2") (pintype "passive"))
      (node (ref "C29") (pin "2") (pinfunction "2_2") (pintype "passive"))
      (node (ref "C3") (pin "2") (pinfunction "2_2") (pintype "passive"))
      (node (ref "C30") (pin "2") (pinfunction "2_2") (pintype "passive"))
      (node (ref "C31") (pin "2") (pinfunction "2_2") (pintype "passive"))
      (node (ref "C32") (pin "2") (pinfunction "2_2") (pintype "passive"))
      (node (ref "C33") (pin "2") (pinfunction "2_2") (pintype "passive"))
      (node (ref "C34") (pin "2") (pinfunction "2_2") (pintype "passive"))
      (node (ref "C35") (pin "2") (pinfunction "2_2") (pintype "passive"))
      (node (ref "C36") (pin "2") (pinfunction "2_2") (pintype "passive"))
      (node (ref "C37") (pin "2") (pinfunction "2_2") (pintype "passive"))
      (node (ref "C38") (pin "2") (pinfunction "2_2") (pintype "passive"))
      (node (ref "C39") (pin "2") (pinfunction "2_2") (pintype "passive"))
      (node (ref "C4") (pin "2") (pinfunction "2_2") (pintype "passive"))
      (node (ref "C40") (pin "2") (pinfunction "2_2") (pintype "passive"))
      (node (ref "C5") (pin "2") (pinfunction "2_2") (pintype "passive"))
      (node (ref "C6") (pin "2") (pinfunction "2_2") (pintype "passive"))
      (node (ref "C7") (pin "2") (pinfunction "2_2") (pintype "passive"))
      (node (ref "C8") (pin "2") (pinfunction "2_2") (pintype "passive"))
      (node (ref "C9") (pin "2") (pinfunction "2_2") (pintype "passive"))
      (node (ref "FB3") (pin "1") (pinfunction "1_1") (pintype "passive"))
      (node (ref "H1") (pin "1") (pinfunction "1_1") (pintype "passive"))
      (node (ref "H1") (pin "29") (pinfunction "29_29") (pintype "passive"))
      (node (ref "H1") (pin "3") (pinfunction "3_3") (pintype "passive"))
      (node (ref "H1") (pin "33") (pinfunction "33_33") (pintype "passive"))
      (node (ref "H1") (pin "4") (pinfunction "4_4") (pintype "passive"))
      (node (ref "H1") (pin "59") (pinfunction "59_59") (pintype "passive"))
      (node (ref "H2") (pin "1") (pinfunction "1_1") (pintype "passive"))
      (node (ref "H3") (pin "1") (pinfunction "1_1") (pintype "passive"))
      (node (ref "H3") (pin "9") (pinfunction "9_9") (pintype "passive"))
      (node (ref "H4") (pin "1") (pinfunction "1_1") (pintype "passive"))
      (node (ref "H4") (pin "17") (pinfunction "17_17") (pintype "passive"))
      (node (ref "H4") (pin "20") (pinfunction "20_20") (pintype "passive"))
      (node (ref "H4") (pin "21") (pinfunction "21_21") (pintype "passive"))
      (node (ref "H4") (pin "24") (pinfunction "24_24") (pintype "passive"))
      (node (ref "H4") (pin "25") (pinfunction "25_25") (pintype "passive"))
      (node (ref "H4") (pin "27") (pinfunction "27_27") (pintype "passive"))
      (node (ref "H4") (pin "28") (pinfunction "28_28") (pintype "passive"))
      (node (ref "H5") (pin "1") (pinfunction "1_1") (pintype "passive"))
      (node (ref "H6") (pin "3") (pinfunction "GND_3") (pintype "passive"))
      (node (ref "H6") (pin "5") (pinfunction "GND_5") (pintype "passive"))
      (node (ref "H6") (pin "9") (pinfunction "GND_9") (pintype "passive"))
      (node (ref "J1") (pin "4") (pinfunction "GND_4") (pintype "power_in"))
      (node (ref "J1") (pin "MH") (pinfunction "SHLD_MH") (pintype "passive"))
      (node (ref "J2") (pin "5") (pinfunction "GND_5") (pintype "passive"))
      (node (ref "J2") (pin "MH") (pinfunction "MH_MH") (pintype "passive"))
      (node (ref "J3") (pin "4") (pinfunction "GND_4") (pintype "passive"))
      (node (ref "J3") (pin "SH") (pinfunction "SHLD_SH") (pintype "passive"))
      (node (ref "R1") (pin "1") (pinfunction "1_1") (pintype "passive"))
      (node (ref "R10") (pin "1") (pinfunction "1_1") (pintype "passive"))
      (node (ref "R11") (pin "1") (pinfunction "1_1") (pintype "passive"))
      (node (ref "R15") (pin "3") (pinfunction "3_3") (pintype "passive"))
      (node (ref "R16") (pin "3") (pinfunction "3_3") (pintype "passive"))
      (node (ref "R17") (pin "3") (pinfunction "3_3") (pintype "passive"))
      (node (ref "R18") (pin "3") (pinfunction "3_3") (pintype "passive"))
      (node (ref "R19") (pin "3") (pinfunction "3_3") (pintype "passive"))
      (node (ref "R7") (pin "1") (pinfunction "1_1") (pintype "passive"))
      (node (ref "S1") (pin "3") (pinfunction "3_3") (pintype "passive"))
      (node (ref "S1") (pin "4") (pinfunction "4_4") (pintype "passive"))
      (node (ref "S1") (pin "5") (pinfunction "GND_5") (pintype "passive"))
      (node (ref "U1") (pin "C4") (pinfunction "VSSIO_C4") (pintype "power_in"))
      (node (ref "U1") (pin "D13") (pinfunction "VSSIO_D13") (pintype "power_in"))
      (node (ref "U1") (pin "G1") (pinfunction "USB0_VSSA_REF_G1") (pintype "power_in"))
      (node (ref "U1") (pin "G6") (pinfunction "VSSIO_G6") (pintype "power_in"))
      (node (ref "U1") (pin "G7") (pinfunction "VSSIO_G7") (pintype "power_in"))
      (node (ref "U1") (pin "G8") (pinfunction "VSSIO_G8") (pintype "power_in"))
      (node (ref "U1") (pin "G9") (pinfunction "VSS_G9") (pintype "power_in"))
      (node (ref "U1") (pin "H3") (pinfunction "USB0_VSSA_TERM_H3") (pintype "power_in"))
      (node (ref "U1") (pin "H7") (pinfunction "VSS_H7") (pintype "power_in"))
      (node (ref "U1") (pin "H8") (pinfunction "VSSIO_H8") (pintype "power_in"))
      (node (ref "U1") (pin "H9") (pinfunction "VSSIO_H9") (pintype "power_in"))
      (node (ref "U1") (pin "J10") (pinfunction "VSS_J10") (pintype "power_in"))
      (node (ref "U1") (pin "J11") (pinfunction "VSS_J11") (pintype "power_in"))
      (node (ref "U1") (pin "J8") (pinfunction "VSSIO_J8") (pintype "power_in"))
      (node (ref "U1") (pin "J9") (pinfunction "VSSIO_J9") (pintype "power_in"))
      (node (ref "U1") (pin "K10") (pinfunction "VSSIO_K10") (pintype "power_in"))
      (node (ref "U1") (pin "K8") (pinfunction "VSS_K8") (pintype "power_in"))
      (node (ref "U1") (pin "K9") (pinfunction "VSSIO_K9") (pintype "power_in"))
      (node (ref "U1") (pin "M13") (pinfunction "VSSIO_M13") (pintype "power_in"))
      (node (ref "U1") (pin "P13") (pinfunction "VSSIO_P13") (pintype "power_in"))
      (node (ref "U1") (pin "P7") (pinfunction "VSSIO_P7") (pintype "power_in"))
      (node (ref "U2") (pin "A1") (pinfunction "VSS_A1") (pintype "power_in"))
      (node (ref "U2") (pin "A3") (pinfunction "VSSQ_A3") (pintype "power_in"))
      (node (ref "U2") (pin "B7") (pinfunction "VSSQ_B7") (pintype "power_in"))
      (node (ref "U2") (pin "C3") (pinfunction "VSSQ_C3") (pintype "power_in"))
      (node (ref "U2") (pin "D7") (pinfunction "VSSQ_D7") (pintype "power_in"))
      (node (ref "U2") (pin "E3") (pinfunction "VSS_E3") (pintype "power_in"))
      (node (ref "U2") (pin "J1") (pinfunction "VSS_J1") (pintype "power_in"))
      (node (ref "U3") (pin "18") (pinfunction "ID_18") (pintype "input"))
      (node (ref "U3") (pin "25") (pinfunction "GND_25") (pintype "power_in"))
      (node (ref "U4") (pin "3") (pinfunction "GND_3") (pintype "power_in"))
      (node (ref "U5") (pin "1") (pinfunction "GND_1") (pintype "power_in"))
      (node (ref "X1") (pin "2") (pinfunction "GND_2") (pintype "passive"))
      (node (ref "X1") (pin "4") (pinfunction "GND_4") (pintype "passive"))
      (node (ref "X2") (pin "2") (pinfunction "GND_2") (pintype "passive"))
      (node (ref "X2") (pin "4") (pinfunction "GND_4") (pintype "passive"))
    )
    (net (code "220") (name "GNDA") (class "Default")
      (node (ref "FB3") (pin "2") (pinfunction "2_2") (pintype "passive"))
      (node (ref "H1") (pin "58") (pinfunction "58_58") (pintype "passive"))
      (node (ref "U1") (pin "B2") (pinfunction "VSSA_B2") (pintype "power_in"))
    )
    (net (code "221") (name "Net-(D1-A)") (class "Default")
      (node (ref "D1") (pin "1") (pinfunction "A_1") (pintype "passive"))
      (node (ref "FB1") (pin "2") (pinfunction "2_2") (pintype "passive"))
    )
    (net (code "222") (name "Net-(D1-K)") (class "Default")
      (node (ref "C39") (pin "1") (pinfunction "1_1") (pintype "passive"))
      (node (ref "D1") (pin "2") (pinfunction "K_2") (pintype "passive"))
      (node (ref "U4") (pin "1") (pinfunction "Vin_1") (pintype "power_in"))
    )
    (net (code "223") (name "Net-(D2-CATHODE)") (class "Default")
      (node (ref "D2") (pin "2") (pinfunction "CATHODE_2") (pintype "passive"))
      (node (ref "R11") (pin "2") (pinfunction "2_2") (pintype "passive"))
    )
    (net (code "224") (name "Net-(U1E-USB0_RREF)") (class "Default")
      (node (ref "R10") (pin "2") (pinfunction "2_2") (pintype "passive"))
      (node (ref "U1") (pin "H1") (pinfunction "USB0_RREF_H1") (pintype "passive"))
    )
    (net (code "225") (name "Net-(U3-RBIAS)") (class "Default")
      (node (ref "R1") (pin "2") (pinfunction "2_2") (pintype "passive"))
      (node (ref "U3") (pin "19") (pinfunction "RBIAS_19") (pintype "passive"))
    )
    (net (code "226") (name "Net-(U3-VDD18)") (class "Default")
      (node (ref "C24") (pin "1") (pinfunction "1_1") (pintype "passive"))
      (node (ref "U3") (pin "23") (pinfunction "VDD18_23") (pintype "power_in"))
    )
    (net (code "227") (name "Net-(U3-VDD33)") (class "Default")
      (node (ref "C25") (pin "1") (pinfunction "1_1") (pintype "passive"))
      (node (ref "U3") (pin "15") (pinfunction "VDD33_15") (pintype "power_in"))
    )
    (net (code "228") (name "USB0_VBUS") (class "Default")
      (node (ref "FB1") (pin "1") (pinfunction "1_1") (pintype "passive"))
      (node (ref "H3") (pin "3") (pinfunction "3_3") (pintype "passive"))
      (node (ref "H3") (pin "4") (pinfunction "4_4") (pintype "passive"))
      (node (ref "J2") (pin "1") (pinfunction "VCC_1") (pintype "passive"))
      (node (ref "U1") (pin "F1") (pinfunction "USB0_VBUS_F1") (pintype "power_in"))
    )
    (net (code "229") (name "VBAT") (class "Default")
      (node (ref "C23") (pin "1") (pinfunction "1_1") (pintype "passive"))
      (node (ref "FB6") (pin "2") (pinfunction "2_2") (pintype "passive"))
      (node (ref "U3") (pin "16") (pinfunction "VBAT_16") (pintype "power_in"))
    )
    (net (code "230") (name "VDD") (class "Default")
      (node (ref "C27") (pin "1") (pinfunction "1_1") (pintype "passive"))
      (node (ref "C32") (pin "1") (pinfunction "1_1") (pintype "passive"))
      (node (ref "C33") (pin "1") (pinfunction "1_1") (pintype "passive"))
      (node (ref "FB5") (pin "1") (pinfunction "1_1") (pintype "passive"))
      (node (ref "R15") (pin "1") (pinfunction "1_1") (pintype "passive"))
      (node (ref "R16") (pin "1") (pinfunction "1_1") (pintype "passive"))
      (node (ref "R17") (pin "1") (pinfunction "1_1") (pintype "passive"))
      (node (ref "R18") (pin "1") (pinfunction "1_1") (pintype "passive"))
      (node (ref "R19") (pin "1") (pinfunction "1_1") (pintype "passive"))
      (node (ref "U2") (pin "A9") (pinfunction "VDD_A9") (pintype "power_in"))
      (node (ref "U2") (pin "E7") (pinfunction "VDD_E7") (pintype "power_in"))
      (node (ref "U2") (pin "J9") (pinfunction "VDD_J9") (pintype "power_in"))
    )
    (net (code "231") (name "VDDA") (class "Default")
      (node (ref "C22") (pin "1") (pinfunction "1_1") (pintype "passive"))
      (node (ref "FB2") (pin "2") (pinfunction "2_2") (pintype "passive"))
      (node (ref "U1") (pin "B4") (pinfunction "VDDA_B4") (pintype "power_in"))
    )
    (net (code "232") (name "VDDIO") (class "Default")
      (node (ref "C26") (pin "1") (pinfunction "1_1") (pintype "passive"))
      (node (ref "FB7") (pin "2") (pinfunction "2_2") (pintype "passive"))
      (node (ref "U3") (pin "9") (pinfunction "VDDIO_9") (pintype "power_in"))
    )
    (net (code "233") (name "VDDQ") (class "Default")
      (node (ref "C28") (pin "1") (pinfunction "1_1") (pintype "passive"))
      (node (ref "C29") (pin "1") (pinfunction "1_1") (pintype "passive"))
      (node (ref "C30") (pin "1") (pinfunction "1_1") (pintype "passive"))
      (node (ref "C31") (pin "1") (pinfunction "1_1") (pintype "passive"))
      (node (ref "FB4") (pin "1") (pinfunction "1_1") (pintype "passive"))
      (node (ref "U2") (pin "A7") (pinfunction "VDDQ_A7") (pintype "power_in"))
      (node (ref "U2") (pin "B3") (pinfunction "VDDQ_B3") (pintype "power_in"))
      (node (ref "U2") (pin "C7") (pinfunction "VDDQ_C7") (pintype "power_in"))
      (node (ref "U2") (pin "D3") (pinfunction "VDDQ_D3") (pintype "power_in"))
    )
    (net (code "234") (name "unconnected-(H6-NC-Pad7)") (class "Default")
      (node (ref "H6") (pin "7") (pinfunction "NC_7") (pintype "passive+no_connect"))
    )
    (net (code "235") (name "unconnected-(S1-Pad1)") (class "Default")
      (node (ref "S1") (pin "1") (pinfunction "1_1") (pintype "passive+no_connect"))
    )
    (net (code "236") (name "unconnected-(U2A-NC-PadE2)") (class "Default")
      (node (ref "U2") (pin "E2") (pinfunction "NC_E2") (pintype "passive+no_connect"))
    )
  )
)
